# Mikrolysreklamen15.net
KiCad netlist of a schematic drawn in Altium Designer
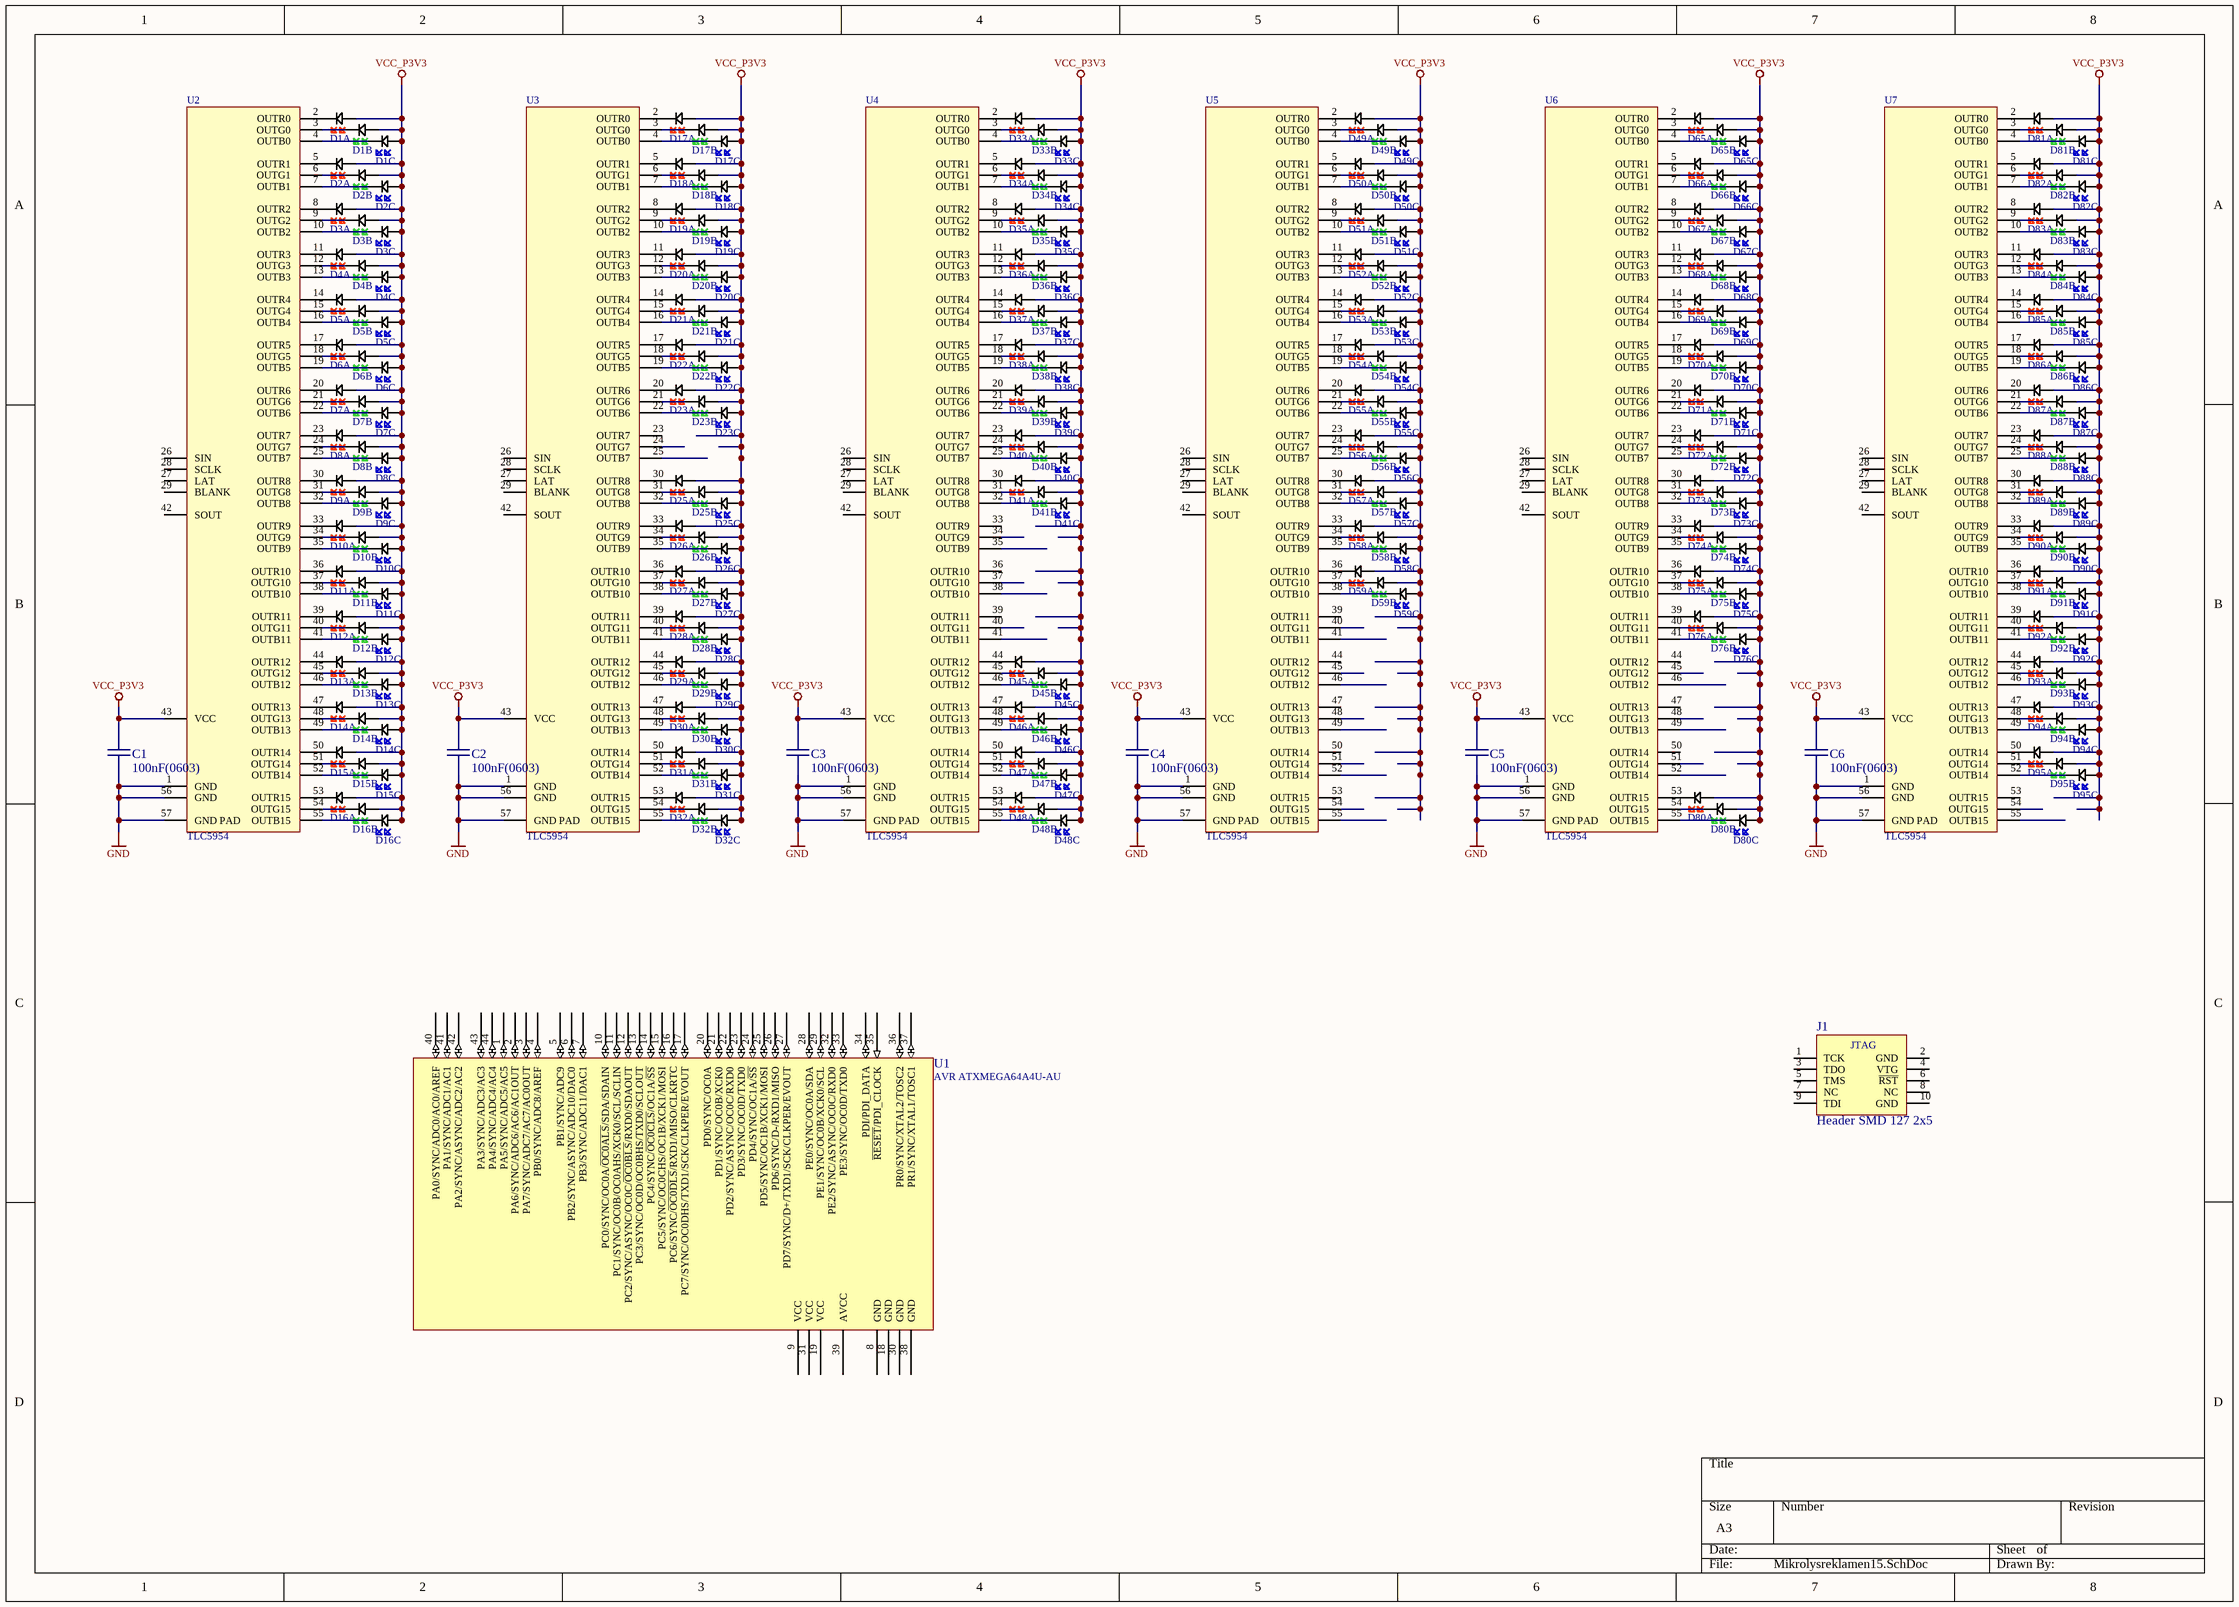
[diagram p0: Mikrolysreklamen15.SchDoc]

(export (version "E")
  (design (tool "Eeschema 10.0.6"))
  (components
    (comp (ref "C1")
      (value "100nF(0603)")
      (footprint "CAPC0603(1608)55_N")
      (description "100nF 0603 5% X7R 50V")
      (libsource (lib "OVLib") (part "CAP"))
    )
    (comp (ref "C2")
      (value "100nF(0603)")
      (footprint "CAPC0603(1608)55_N")
      (description "100nF 0603 5% X7R 50V")
      (libsource (lib "OVLib") (part "CAP"))
    )
    (comp (ref "C3")
      (value "100nF(0603)")
      (footprint "CAPC0603(1608)55_N")
      (description "100nF 0603 5% X7R 50V")
      (libsource (lib "OVLib") (part "CAP"))
    )
    (comp (ref "C4")
      (value "100nF(0603)")
      (footprint "CAPC0603(1608)55_N")
      (description "100nF 0603 5% X7R 50V")
      (libsource (lib "OVLib") (part "CAP"))
    )
    (comp (ref "C5")
      (value "100nF(0603)")
      (footprint "CAPC0603(1608)55_N")
      (description "100nF 0603 5% X7R 50V")
      (libsource (lib "OVLib") (part "CAP"))
    )
    (comp (ref "C6")
      (value "100nF(0603)")
      (footprint "CAPC0603(1608)55_N")
      (description "100nF 0603 5% X7R 50V")
      (libsource (lib "OVLib") (part "CAP"))
    )
    (comp (ref "D1")
      (value "SX-0402-RGB SMD LED")
      (footprint "LED0402SX_N")
      (description "1010 (metric) SMD RGB LED")
      (libsource (lib "OVLib") (part "LED_RGB_CA_CHIP"))
    )
    (comp (ref "D2")
      (value "SX-0402-RGB SMD LED")
      (footprint "LED0402SX_N")
      (description "1010 (metric) SMD RGB LED")
      (libsource (lib "OVLib") (part "LED_RGB_CA_CHIP"))
    )
    (comp (ref "D3")
      (value "SX-0402-RGB SMD LED")
      (footprint "LED0402SX_N")
      (description "1010 (metric) SMD RGB LED")
      (libsource (lib "OVLib") (part "LED_RGB_CA_CHIP"))
    )
    (comp (ref "D4")
      (value "SX-0402-RGB SMD LED")
      (footprint "LED0402SX_N")
      (description "1010 (metric) SMD RGB LED")
      (libsource (lib "OVLib") (part "LED_RGB_CA_CHIP"))
    )
    (comp (ref "D5")
      (value "SX-0402-RGB SMD LED")
      (footprint "LED0402SX_N")
      (description "1010 (metric) SMD RGB LED")
      (libsource (lib "OVLib") (part "LED_RGB_CA_CHIP"))
    )
    (comp (ref "D6")
      (value "SX-0402-RGB SMD LED")
      (footprint "LED0402SX_N")
      (description "1010 (metric) SMD RGB LED")
      (libsource (lib "OVLib") (part "LED_RGB_CA_CHIP"))
    )
    (comp (ref "D7")
      (value "SX-0402-RGB SMD LED")
      (footprint "LED0402SX_N")
      (description "1010 (metric) SMD RGB LED")
      (libsource (lib "OVLib") (part "LED_RGB_CA_CHIP"))
    )
    (comp (ref "D8")
      (value "SX-0402-RGB SMD LED")
      (footprint "LED0402SX_N")
      (description "1010 (metric) SMD RGB LED")
      (libsource (lib "OVLib") (part "LED_RGB_CA_CHIP"))
    )
    (comp (ref "D9")
      (value "SX-0402-RGB SMD LED")
      (footprint "LED0402SX_N")
      (description "1010 (metric) SMD RGB LED")
      (libsource (lib "OVLib") (part "LED_RGB_CA_CHIP"))
    )
    (comp (ref "D10")
      (value "SX-0402-RGB SMD LED")
      (footprint "LED0402SX_N")
      (description "1010 (metric) SMD RGB LED")
      (libsource (lib "OVLib") (part "LED_RGB_CA_CHIP"))
    )
    (comp (ref "D11")
      (value "SX-0402-RGB SMD LED")
      (footprint "LED0402SX_N")
      (description "1010 (metric) SMD RGB LED")
      (libsource (lib "OVLib") (part "LED_RGB_CA_CHIP"))
    )
    (comp (ref "D12")
      (value "SX-0402-RGB SMD LED")
      (footprint "LED0402SX_N")
      (description "1010 (metric) SMD RGB LED")
      (libsource (lib "OVLib") (part "LED_RGB_CA_CHIP"))
    )
    (comp (ref "D13")
      (value "SX-0402-RGB SMD LED")
      (footprint "LED0402SX_N")
      (description "1010 (metric) SMD RGB LED")
      (libsource (lib "OVLib") (part "LED_RGB_CA_CHIP"))
    )
    (comp (ref "D14")
      (value "SX-0402-RGB SMD LED")
      (footprint "LED0402SX_N")
      (description "1010 (metric) SMD RGB LED")
      (libsource (lib "OVLib") (part "LED_RGB_CA_CHIP"))
    )
    (comp (ref "D15")
      (value "SX-0402-RGB SMD LED")
      (footprint "LED0402SX_N")
      (description "1010 (metric) SMD RGB LED")
      (libsource (lib "OVLib") (part "LED_RGB_CA_CHIP"))
    )
    (comp (ref "D16")
      (value "SX-0402-RGB SMD LED")
      (footprint "LED0402SX_N")
      (description "1010 (metric) SMD RGB LED")
      (libsource (lib "OVLib") (part "LED_RGB_CA_CHIP"))
    )
    (comp (ref "D17")
      (value "SX-0402-RGB SMD LED")
      (footprint "LED0402SX_N")
      (description "1010 (metric) SMD RGB LED")
      (libsource (lib "OVLib") (part "LED_RGB_CA_CHIP"))
    )
    (comp (ref "D18")
      (value "SX-0402-RGB SMD LED")
      (footprint "LED0402SX_N")
      (description "1010 (metric) SMD RGB LED")
      (libsource (lib "OVLib") (part "LED_RGB_CA_CHIP"))
    )
    (comp (ref "D19")
      (value "SX-0402-RGB SMD LED")
      (footprint "LED0402SX_N")
      (description "1010 (metric) SMD RGB LED")
      (libsource (lib "OVLib") (part "LED_RGB_CA_CHIP"))
    )
    (comp (ref "D20")
      (value "SX-0402-RGB SMD LED")
      (footprint "LED0402SX_N")
      (description "1010 (metric) SMD RGB LED")
      (libsource (lib "OVLib") (part "LED_RGB_CA_CHIP"))
    )
    (comp (ref "D21")
      (value "SX-0402-RGB SMD LED")
      (footprint "LED0402SX_N")
      (description "1010 (metric) SMD RGB LED")
      (libsource (lib "OVLib") (part "LED_RGB_CA_CHIP"))
    )
    (comp (ref "D22")
      (value "SX-0402-RGB SMD LED")
      (footprint "LED0402SX_N")
      (description "1010 (metric) SMD RGB LED")
      (libsource (lib "OVLib") (part "LED_RGB_CA_CHIP"))
    )
    (comp (ref "D23")
      (value "SX-0402-RGB SMD LED")
      (footprint "LED0402SX_N")
      (description "1010 (metric) SMD RGB LED")
      (libsource (lib "OVLib") (part "LED_RGB_CA_CHIP"))
    )
    (comp (ref "D25")
      (value "SX-0402-RGB SMD LED")
      (footprint "LED0402SX_N")
      (description "1010 (metric) SMD RGB LED")
      (libsource (lib "OVLib") (part "LED_RGB_CA_CHIP"))
    )
    (comp (ref "D26")
      (value "SX-0402-RGB SMD LED")
      (footprint "LED0402SX_N")
      (description "1010 (metric) SMD RGB LED")
      (libsource (lib "OVLib") (part "LED_RGB_CA_CHIP"))
    )
    (comp (ref "D27")
      (value "SX-0402-RGB SMD LED")
      (footprint "LED0402SX_N")
      (description "1010 (metric) SMD RGB LED")
      (libsource (lib "OVLib") (part "LED_RGB_CA_CHIP"))
    )
    (comp (ref "D28")
      (value "SX-0402-RGB SMD LED")
      (footprint "LED0402SX_N")
      (description "1010 (metric) SMD RGB LED")
      (libsource (lib "OVLib") (part "LED_RGB_CA_CHIP"))
    )
    (comp (ref "D29")
      (value "SX-0402-RGB SMD LED")
      (footprint "LED0402SX_N")
      (description "1010 (metric) SMD RGB LED")
      (libsource (lib "OVLib") (part "LED_RGB_CA_CHIP"))
    )
    (comp (ref "D30")
      (value "SX-0402-RGB SMD LED")
      (footprint "LED0402SX_N")
      (description "1010 (metric) SMD RGB LED")
      (libsource (lib "OVLib") (part "LED_RGB_CA_CHIP"))
    )
    (comp (ref "D31")
      (value "SX-0402-RGB SMD LED")
      (footprint "LED0402SX_N")
      (description "1010 (metric) SMD RGB LED")
      (libsource (lib "OVLib") (part "LED_RGB_CA_CHIP"))
    )
    (comp (ref "D32")
      (value "SX-0402-RGB SMD LED")
      (footprint "LED0402SX_N")
      (description "1010 (metric) SMD RGB LED")
      (libsource (lib "OVLib") (part "LED_RGB_CA_CHIP"))
    )
    (comp (ref "D33")
      (value "SX-0402-RGB SMD LED")
      (footprint "LED0402SX_N")
      (description "1010 (metric) SMD RGB LED")
      (libsource (lib "OVLib") (part "LED_RGB_CA_CHIP"))
    )
    (comp (ref "D34")
      (value "SX-0402-RGB SMD LED")
      (footprint "LED0402SX_N")
      (description "1010 (metric) SMD RGB LED")
      (libsource (lib "OVLib") (part "LED_RGB_CA_CHIP"))
    )
    (comp (ref "D35")
      (value "SX-0402-RGB SMD LED")
      (footprint "LED0402SX_N")
      (description "1010 (metric) SMD RGB LED")
      (libsource (lib "OVLib") (part "LED_RGB_CA_CHIP"))
    )
    (comp (ref "D36")
      (value "SX-0402-RGB SMD LED")
      (footprint "LED0402SX_N")
      (description "1010 (metric) SMD RGB LED")
      (libsource (lib "OVLib") (part "LED_RGB_CA_CHIP"))
    )
    (comp (ref "D37")
      (value "SX-0402-RGB SMD LED")
      (footprint "LED0402SX_N")
      (description "1010 (metric) SMD RGB LED")
      (libsource (lib "OVLib") (part "LED_RGB_CA_CHIP"))
    )
    (comp (ref "D38")
      (value "SX-0402-RGB SMD LED")
      (footprint "LED0402SX_N")
      (description "1010 (metric) SMD RGB LED")
      (libsource (lib "OVLib") (part "LED_RGB_CA_CHIP"))
    )
    (comp (ref "D39")
      (value "SX-0402-RGB SMD LED")
      (footprint "LED0402SX_N")
      (description "1010 (metric) SMD RGB LED")
      (libsource (lib "OVLib") (part "LED_RGB_CA_CHIP"))
    )
    (comp (ref "D40")
      (value "SX-0402-RGB SMD LED")
      (footprint "LED0402SX_N")
      (description "1010 (metric) SMD RGB LED")
      (libsource (lib "OVLib") (part "LED_RGB_CA_CHIP"))
    )
    (comp (ref "D41")
      (value "SX-0402-RGB SMD LED")
      (footprint "LED0402SX_N")
      (description "1010 (metric) SMD RGB LED")
      (libsource (lib "OVLib") (part "LED_RGB_CA_CHIP"))
    )
    (comp (ref "D45")
      (value "SX-0402-RGB SMD LED")
      (footprint "LED0402SX_N")
      (description "1010 (metric) SMD RGB LED")
      (libsource (lib "OVLib") (part "LED_RGB_CA_CHIP"))
    )
    (comp (ref "D46")
      (value "SX-0402-RGB SMD LED")
      (footprint "LED0402SX_N")
      (description "1010 (metric) SMD RGB LED")
      (libsource (lib "OVLib") (part "LED_RGB_CA_CHIP"))
    )
    (comp (ref "D47")
      (value "SX-0402-RGB SMD LED")
      (footprint "LED0402SX_N")
      (description "1010 (metric) SMD RGB LED")
      (libsource (lib "OVLib") (part "LED_RGB_CA_CHIP"))
    )
    (comp (ref "D48")
      (value "SX-0402-RGB SMD LED")
      (footprint "LED0402SX_N")
      (description "1010 (metric) SMD RGB LED")
      (libsource (lib "OVLib") (part "LED_RGB_CA_CHIP"))
    )
    (comp (ref "D49")
      (value "SX-0402-RGB SMD LED")
      (footprint "LED0402SX_N")
      (description "1010 (metric) SMD RGB LED")
      (libsource (lib "OVLib") (part "LED_RGB_CA_CHIP"))
    )
    (comp (ref "D50")
      (value "SX-0402-RGB SMD LED")
      (footprint "LED0402SX_N")
      (description "1010 (metric) SMD RGB LED")
      (libsource (lib "OVLib") (part "LED_RGB_CA_CHIP"))
    )
    (comp (ref "D51")
      (value "SX-0402-RGB SMD LED")
      (footprint "LED0402SX_N")
      (description "1010 (metric) SMD RGB LED")
      (libsource (lib "OVLib") (part "LED_RGB_CA_CHIP"))
    )
    (comp (ref "D52")
      (value "SX-0402-RGB SMD LED")
      (footprint "LED0402SX_N")
      (description "1010 (metric) SMD RGB LED")
      (libsource (lib "OVLib") (part "LED_RGB_CA_CHIP"))
    )
    (comp (ref "D53")
      (value "SX-0402-RGB SMD LED")
      (footprint "LED0402SX_N")
      (description "1010 (metric) SMD RGB LED")
      (libsource (lib "OVLib") (part "LED_RGB_CA_CHIP"))
    )
    (comp (ref "D54")
      (value "SX-0402-RGB SMD LED")
      (footprint "LED0402SX_N")
      (description "1010 (metric) SMD RGB LED")
      (libsource (lib "OVLib") (part "LED_RGB_CA_CHIP"))
    )
    (comp (ref "D55")
      (value "SX-0402-RGB SMD LED")
      (footprint "LED0402SX_N")
      (description "1010 (metric) SMD RGB LED")
      (libsource (lib "OVLib") (part "LED_RGB_CA_CHIP"))
    )
    (comp (ref "D56")
      (value "SX-0402-RGB SMD LED")
      (footprint "LED0402SX_N")
      (description "1010 (metric) SMD RGB LED")
      (libsource (lib "OVLib") (part "LED_RGB_CA_CHIP"))
    )
    (comp (ref "D57")
      (value "SX-0402-RGB SMD LED")
      (footprint "LED0402SX_N")
      (description "1010 (metric) SMD RGB LED")
      (libsource (lib "OVLib") (part "LED_RGB_CA_CHIP"))
    )
    (comp (ref "D58")
      (value "SX-0402-RGB SMD LED")
      (footprint "LED0402SX_N")
      (description "1010 (metric) SMD RGB LED")
      (libsource (lib "OVLib") (part "LED_RGB_CA_CHIP"))
    )
    (comp (ref "D59")
      (value "SX-0402-RGB SMD LED")
      (footprint "LED0402SX_N")
      (description "1010 (metric) SMD RGB LED")
      (libsource (lib "OVLib") (part "LED_RGB_CA_CHIP"))
    )
    (comp (ref "D65")
      (value "SX-0402-RGB SMD LED")
      (footprint "LED0402SX_N")
      (description "1010 (metric) SMD RGB LED")
      (libsource (lib "OVLib") (part "LED_RGB_CA_CHIP"))
    )
    (comp (ref "D66")
      (value "SX-0402-RGB SMD LED")
      (footprint "LED0402SX_N")
      (description "1010 (metric) SMD RGB LED")
      (libsource (lib "OVLib") (part "LED_RGB_CA_CHIP"))
    )
    (comp (ref "D67")
      (value "SX-0402-RGB SMD LED")
      (footprint "LED0402SX_N")
      (description "1010 (metric) SMD RGB LED")
      (libsource (lib "OVLib") (part "LED_RGB_CA_CHIP"))
    )
    (comp (ref "D68")
      (value "SX-0402-RGB SMD LED")
      (footprint "LED0402SX_N")
      (description "1010 (metric) SMD RGB LED")
      (libsource (lib "OVLib") (part "LED_RGB_CA_CHIP"))
    )
    (comp (ref "D69")
      (value "SX-0402-RGB SMD LED")
      (footprint "LED0402SX_N")
      (description "1010 (metric) SMD RGB LED")
      (libsource (lib "OVLib") (part "LED_RGB_CA_CHIP"))
    )
    (comp (ref "D70")
      (value "SX-0402-RGB SMD LED")
      (footprint "LED0402SX_N")
      (description "1010 (metric) SMD RGB LED")
      (libsource (lib "OVLib") (part "LED_RGB_CA_CHIP"))
    )
    (comp (ref "D71")
      (value "SX-0402-RGB SMD LED")
      (footprint "LED0402SX_N")
      (description "1010 (metric) SMD RGB LED")
      (libsource (lib "OVLib") (part "LED_RGB_CA_CHIP"))
    )
    (comp (ref "D72")
      (value "SX-0402-RGB SMD LED")
      (footprint "LED0402SX_N")
      (description "1010 (metric) SMD RGB LED")
      (libsource (lib "OVLib") (part "LED_RGB_CA_CHIP"))
    )
    (comp (ref "D73")
      (value "SX-0402-RGB SMD LED")
      (footprint "LED0402SX_N")
      (description "1010 (metric) SMD RGB LED")
      (libsource (lib "OVLib") (part "LED_RGB_CA_CHIP"))
    )
    (comp (ref "D74")
      (value "SX-0402-RGB SMD LED")
      (footprint "LED0402SX_N")
      (description "1010 (metric) SMD RGB LED")
      (libsource (lib "OVLib") (part "LED_RGB_CA_CHIP"))
    )
    (comp (ref "D75")
      (value "SX-0402-RGB SMD LED")
      (footprint "LED0402SX_N")
      (description "1010 (metric) SMD RGB LED")
      (libsource (lib "OVLib") (part "LED_RGB_CA_CHIP"))
    )
    (comp (ref "D76")
      (value "SX-0402-RGB SMD LED")
      (footprint "LED0402SX_N")
      (description "1010 (metric) SMD RGB LED")
      (libsource (lib "OVLib") (part "LED_RGB_CA_CHIP"))
    )
    (comp (ref "D80")
      (value "SX-0402-RGB SMD LED")
      (footprint "LED0402SX_N")
      (description "1010 (metric) SMD RGB LED")
      (libsource (lib "OVLib") (part "LED_RGB_CA_CHIP"))
    )
    (comp (ref "D81")
      (value "SX-0402-RGB SMD LED")
      (footprint "LED0402SX_N")
      (description "1010 (metric) SMD RGB LED")
      (libsource (lib "OVLib") (part "LED_RGB_CA_CHIP"))
    )
    (comp (ref "D82")
      (value "SX-0402-RGB SMD LED")
      (footprint "LED0402SX_N")
      (description "1010 (metric) SMD RGB LED")
      (libsource (lib "OVLib") (part "LED_RGB_CA_CHIP"))
    )
    (comp (ref "D83")
      (value "SX-0402-RGB SMD LED")
      (footprint "LED0402SX_N")
      (description "1010 (metric) SMD RGB LED")
      (libsource (lib "OVLib") (part "LED_RGB_CA_CHIP"))
    )
    (comp (ref "D84")
      (value "SX-0402-RGB SMD LED")
      (footprint "LED0402SX_N")
      (description "1010 (metric) SMD RGB LED")
      (libsource (lib "OVLib") (part "LED_RGB_CA_CHIP"))
    )
    (comp (ref "D85")
      (value "SX-0402-RGB SMD LED")
      (footprint "LED0402SX_N")
      (description "1010 (metric) SMD RGB LED")
      (libsource (lib "OVLib") (part "LED_RGB_CA_CHIP"))
    )
    (comp (ref "D86")
      (value "SX-0402-RGB SMD LED")
      (footprint "LED0402SX_N")
      (description "1010 (metric) SMD RGB LED")
      (libsource (lib "OVLib") (part "LED_RGB_CA_CHIP"))
    )
    (comp (ref "D87")
      (value "SX-0402-RGB SMD LED")
      (footprint "LED0402SX_N")
      (description "1010 (metric) SMD RGB LED")
      (libsource (lib "OVLib") (part "LED_RGB_CA_CHIP"))
    )
    (comp (ref "D88")
      (value "SX-0402-RGB SMD LED")
      (footprint "LED0402SX_N")
      (description "1010 (metric) SMD RGB LED")
      (libsource (lib "OVLib") (part "LED_RGB_CA_CHIP"))
    )
    (comp (ref "D89")
      (value "SX-0402-RGB SMD LED")
      (footprint "LED0402SX_N")
      (description "1010 (metric) SMD RGB LED")
      (libsource (lib "OVLib") (part "LED_RGB_CA_CHIP"))
    )
    (comp (ref "D90")
      (value "SX-0402-RGB SMD LED")
      (footprint "LED0402SX_N")
      (description "1010 (metric) SMD RGB LED")
      (libsource (lib "OVLib") (part "LED_RGB_CA_CHIP"))
    )
    (comp (ref "D91")
      (value "SX-0402-RGB SMD LED")
      (footprint "LED0402SX_N")
      (description "1010 (metric) SMD RGB LED")
      (libsource (lib "OVLib") (part "LED_RGB_CA_CHIP"))
    )
    (comp (ref "D92")
      (value "SX-0402-RGB SMD LED")
      (footprint "LED0402SX_N")
      (description "1010 (metric) SMD RGB LED")
      (libsource (lib "OVLib") (part "LED_RGB_CA_CHIP"))
    )
    (comp (ref "D93")
      (value "SX-0402-RGB SMD LED")
      (footprint "LED0402SX_N")
      (description "1010 (metric) SMD RGB LED")
      (libsource (lib "OVLib") (part "LED_RGB_CA_CHIP"))
    )
    (comp (ref "D94")
      (value "SX-0402-RGB SMD LED")
      (footprint "LED0402SX_N")
      (description "1010 (metric) SMD RGB LED")
      (libsource (lib "OVLib") (part "LED_RGB_CA_CHIP"))
    )
    (comp (ref "D95")
      (value "SX-0402-RGB SMD LED")
      (footprint "LED0402SX_N")
      (description "1010 (metric) SMD RGB LED")
      (libsource (lib "OVLib") (part "LED_RGB_CA_CHIP"))
    )
    (comp (ref "J1")
      (value "Header SMD 127 2x5")
      (footprint "SMDHDRV10P127_2X5_615X330X560B")
      (description "1,27mm Pitch SMD Header")
      (libsource (lib "OVLib") (part "AVRJTAG"))
    )
    (comp (ref "U1")
      (value "AVR ATXMEGA64A4U-AU")
      (footprint "TQFP80P1200X1200X120-44N")
      (description "Mikrokontroller")
      (libsource (lib "OVLib") (part "ATXMEGA-A4U"))
    )
    (comp (ref "U2")
      (value "TLC5954")
      (footprint "TQFN05P815X815X10-56_N")
      (description "48ch LED Driver with Global Brightness Control, LED Open/Short Detection and Power-Save Mode")
      (libsource (lib "OVLib") (part "TLC5954"))
    )
    (comp (ref "U3")
      (value "TLC5954")
      (footprint "TQFN05P815X815X10-56_N")
      (description "48ch LED Driver with Global Brightness Control, LED Open/Short Detection and Power-Save Mode")
      (libsource (lib "OVLib") (part "TLC5954"))
    )
    (comp (ref "U4")
      (value "TLC5954")
      (footprint "TQFN05P815X815X10-56_N")
      (description "48ch LED Driver with Global Brightness Control, LED Open/Short Detection and Power-Save Mode")
      (libsource (lib "OVLib") (part "TLC5954"))
    )
    (comp (ref "U5")
      (value "TLC5954")
      (footprint "TQFN05P815X815X10-56_N")
      (description "48ch LED Driver with Global Brightness Control, LED Open/Short Detection and Power-Save Mode")
      (libsource (lib "OVLib") (part "TLC5954"))
    )
    (comp (ref "U6")
      (value "TLC5954")
      (footprint "TQFN05P815X815X10-56_N")
      (description "48ch LED Driver with Global Brightness Control, LED Open/Short Detection and Power-Save Mode")
      (libsource (lib "OVLib") (part "TLC5954"))
    )
    (comp (ref "U7")
      (value "TLC5954")
      (footprint "TQFN05P815X815X10-56_N")
      (description "48ch LED Driver with Global Brightness Control, LED Open/Short Detection and Power-Save Mode")
      (libsource (lib "OVLib") (part "TLC5954"))
    )
  )
  (nets
    (net (code "1") (name "GND") (class "Default")
      (node (ref "C1") (pin "1") (pinfunction "1_1") (pintype "passive"))
      (node (ref "C2") (pin "1") (pinfunction "1_1") (pintype "passive"))
      (node (ref "C3") (pin "1") (pinfunction "1_1") (pintype "passive"))
      (node (ref "C4") (pin "1") (pinfunction "1_1") (pintype "passive"))
      (node (ref "C5") (pin "1") (pinfunction "1_1") (pintype "passive"))
      (node (ref "C6") (pin "1") (pinfunction "1_1") (pintype "passive"))
      (node (ref "U2") (pin "1") (pinfunction "GND_1") (pintype "passive"))
      (node (ref "U2") (pin "56") (pinfunction "GND_56") (pintype "passive"))
      (node (ref "U2") (pin "57") (pinfunction "GND_PAD_57") (pintype "passive"))
      (node (ref "U3") (pin "1") (pinfunction "GND_1") (pintype "passive"))
      (node (ref "U3") (pin "56") (pinfunction "GND_56") (pintype "passive"))
      (node (ref "U3") (pin "57") (pinfunction "GND_PAD_57") (pintype "passive"))
      (node (ref "U4") (pin "1") (pinfunction "GND_1") (pintype "passive"))
      (node (ref "U4") (pin "56") (pinfunction "GND_56") (pintype "passive"))
      (node (ref "U4") (pin "57") (pinfunction "GND_PAD_57") (pintype "passive"))
      (node (ref "U5") (pin "1") (pinfunction "GND_1") (pintype "passive"))
      (node (ref "U5") (pin "56") (pinfunction "GND_56") (pintype "passive"))
      (node (ref "U5") (pin "57") (pinfunction "GND_PAD_57") (pintype "passive"))
      (node (ref "U6") (pin "1") (pinfunction "GND_1") (pintype "passive"))
      (node (ref "U6") (pin "56") (pinfunction "GND_56") (pintype "passive"))
      (node (ref "U6") (pin "57") (pinfunction "GND_PAD_57") (pintype "passive"))
      (node (ref "U7") (pin "1") (pinfunction "GND_1") (pintype "passive"))
      (node (ref "U7") (pin "56") (pinfunction "GND_56") (pintype "passive"))
      (node (ref "U7") (pin "57") (pinfunction "GND_PAD_57") (pintype "passive"))
    )
    (net (code "2") (name "Net-(U2-OUTB0)") (class "Default")
      (node (ref "D1") (pin "4") (pinfunction "4_4") (pintype "passive"))
      (node (ref "U2") (pin "4") (pinfunction "OUTB0_4") (pintype "passive"))
    )
    (net (code "3") (name "Net-(U2-OUTB1)") (class "Default")
      (node (ref "D2") (pin "4") (pinfunction "4_4") (pintype "passive"))
      (node (ref "U2") (pin "7") (pinfunction "OUTB1_7") (pintype "passive"))
    )
    (net (code "4") (name "Net-(U2-OUTB2)") (class "Default")
      (node (ref "D3") (pin "4") (pinfunction "4_4") (pintype "passive"))
      (node (ref "U2") (pin "10") (pinfunction "OUTB2_10") (pintype "passive"))
    )
    (net (code "5") (name "Net-(U2-OUTB3)") (class "Default")
      (node (ref "D4") (pin "4") (pinfunction "4_4") (pintype "passive"))
      (node (ref "U2") (pin "13") (pinfunction "OUTB3_13") (pintype "passive"))
    )
    (net (code "6") (name "Net-(U2-OUTB4)") (class "Default")
      (node (ref "D5") (pin "4") (pinfunction "4_4") (pintype "passive"))
      (node (ref "U2") (pin "16") (pinfunction "OUTB4_16") (pintype "passive"))
    )
    (net (code "7") (name "Net-(U2-OUTB5)") (class "Default")
      (node (ref "D6") (pin "4") (pinfunction "4_4") (pintype "passive"))
      (node (ref "U2") (pin "19") (pinfunction "OUTB5_19") (pintype "passive"))
    )
    (net (code "8") (name "Net-(U2-OUTB6)") (class "Default")
      (node (ref "D7") (pin "4") (pinfunction "4_4") (pintype "passive"))
      (node (ref "U2") (pin "22") (pinfunction "OUTB6_22") (pintype "passive"))
    )
    (net (code "9") (name "Net-(U2-OUTB7)") (class "Default")
      (node (ref "D8") (pin "4") (pinfunction "4_4") (pintype "passive"))
      (node (ref "U2") (pin "25") (pinfunction "OUTB7_25") (pintype "passive"))
    )
    (net (code "10") (name "Net-(U2-OUTB8)") (class "Default")
      (node (ref "D9") (pin "4") (pinfunction "4_4") (pintype "passive"))
      (node (ref "U2") (pin "32") (pinfunction "OUTB8_32") (pintype "passive"))
    )
    (net (code "11") (name "Net-(U2-OUTB9)") (class "Default")
      (node (ref "D10") (pin "4") (pinfunction "4_4") (pintype "passive"))
      (node (ref "U2") (pin "35") (pinfunction "OUTB9_35") (pintype "passive"))
    )
    (net (code "12") (name "Net-(U2-OUTB10)") (class "Default")
      (node (ref "D11") (pin "4") (pinfunction "4_4") (pintype "passive"))
      (node (ref "U2") (pin "38") (pinfunction "OUTB10_38") (pintype "passive"))
    )
    (net (code "13") (name "Net-(U2-OUTB11)") (class "Default")
      (node (ref "D12") (pin "4") (pinfunction "4_4") (pintype "passive"))
      (node (ref "U2") (pin "41") (pinfunction "OUTB11_41") (pintype "passive"))
    )
    (net (code "14") (name "Net-(U2-OUTB12)") (class "Default")
      (node (ref "D13") (pin "4") (pinfunction "4_4") (pintype "passive"))
      (node (ref "U2") (pin "46") (pinfunction "OUTB12_46") (pintype "passive"))
    )
    (net (code "15") (name "Net-(U2-OUTB13)") (class "Default")
      (node (ref "D14") (pin "4") (pinfunction "4_4") (pintype "passive"))
      (node (ref "U2") (pin "49") (pinfunction "OUTB13_49") (pintype "passive"))
    )
    (net (code "16") (name "Net-(U2-OUTB14)") (class "Default")
      (node (ref "D15") (pin "4") (pinfunction "4_4") (pintype "passive"))
      (node (ref "U2") (pin "52") (pinfunction "OUTB14_52") (pintype "passive"))
    )
    (net (code "17") (name "Net-(U2-OUTB15)") (class "Default")
      (node (ref "D16") (pin "4") (pinfunction "4_4") (pintype "passive"))
      (node (ref "U2") (pin "55") (pinfunction "OUTB15_55") (pintype "passive"))
    )
    (net (code "18") (name "Net-(U2-OUTG0)") (class "Default")
      (node (ref "D1") (pin "3") (pinfunction "3_3") (pintype "passive"))
      (node (ref "U2") (pin "3") (pinfunction "OUTG0_3") (pintype "passive"))
    )
    (net (code "19") (name "Net-(U2-OUTG1)") (class "Default")
      (node (ref "D2") (pin "3") (pinfunction "3_3") (pintype "passive"))
      (node (ref "U2") (pin "6") (pinfunction "OUTG1_6") (pintype "passive"))
    )
    (net (code "20") (name "Net-(U2-OUTG2)") (class "Default")
      (node (ref "D3") (pin "3") (pinfunction "3_3") (pintype "passive"))
      (node (ref "U2") (pin "9") (pinfunction "OUTG2_9") (pintype "passive"))
    )
    (net (code "21") (name "Net-(U2-OUTG3)") (class "Default")
      (node (ref "D4") (pin "3") (pinfunction "3_3") (pintype "passive"))
      (node (ref "U2") (pin "12") (pinfunction "OUTG3_12") (pintype "passive"))
    )
    (net (code "22") (name "Net-(U2-OUTG4)") (class "Default")
      (node (ref "D5") (pin "3") (pinfunction "3_3") (pintype "passive"))
      (node (ref "U2") (pin "15") (pinfunction "OUTG4_15") (pintype "passive"))
    )
    (net (code "23") (name "Net-(U2-OUTG5)") (class "Default")
      (node (ref "D6") (pin "3") (pinfunction "3_3") (pintype "passive"))
      (node (ref "U2") (pin "18") (pinfunction "OUTG5_18") (pintype "passive"))
    )
    (net (code "24") (name "Net-(U2-OUTG6)") (class "Default")
      (node (ref "D7") (pin "3") (pinfunction "3_3") (pintype "passive"))
      (node (ref "U2") (pin "21") (pinfunction "OUTG6_21") (pintype "passive"))
    )
    (net (code "25") (name "Net-(U2-OUTG7)") (class "Default")
      (node (ref "D8") (pin "3") (pinfunction "3_3") (pintype "passive"))
      (node (ref "U2") (pin "24") (pinfunction "OUTG7_24") (pintype "passive"))
    )
    (net (code "26") (name "Net-(U2-OUTG8)") (class "Default")
      (node (ref "D9") (pin "3") (pinfunction "3_3") (pintype "passive"))
      (node (ref "U2") (pin "31") (pinfunction "OUTG8_31") (pintype "passive"))
    )
    (net (code "27") (name "Net-(U2-OUTG9)") (class "Default")
      (node (ref "D10") (pin "3") (pinfunction "3_3") (pintype "passive"))
      (node (ref "U2") (pin "34") (pinfunction "OUTG9_34") (pintype "passive"))
    )
    (net (code "28") (name "Net-(U2-OUTG10)") (class "Default")
      (node (ref "D11") (pin "3") (pinfunction "3_3") (pintype "passive"))
      (node (ref "U2") (pin "37") (pinfunction "OUTG10_37") (pintype "passive"))
    )
    (net (code "29") (name "Net-(U2-OUTG11)") (class "Default")
      (node (ref "D12") (pin "3") (pinfunction "3_3") (pintype "passive"))
      (node (ref "U2") (pin "40") (pinfunction "OUTG11_40") (pintype "passive"))
    )
    (net (code "30") (name "Net-(U2-OUTG12)") (class "Default")
      (node (ref "D13") (pin "3") (pinfunction "3_3") (pintype "passive"))
      (node (ref "U2") (pin "45") (pinfunction "OUTG12_45") (pintype "passive"))
    )
    (net (code "31") (name "Net-(U2-OUTG13)") (class "Default")
      (node (ref "D14") (pin "3") (pinfunction "3_3") (pintype "passive"))
      (node (ref "U2") (pin "48") (pinfunction "OUTG13_48") (pintype "passive"))
    )
    (net (code "32") (name "Net-(U2-OUTG14)") (class "Default")
      (node (ref "D15") (pin "3") (pinfunction "3_3") (pintype "passive"))
      (node (ref "U2") (pin "51") (pinfunction "OUTG14_51") (pintype "passive"))
    )
    (net (code "33") (name "Net-(U2-OUTG15)") (class "Default")
      (node (ref "D16") (pin "3") (pinfunction "3_3") (pintype "passive"))
      (node (ref "U2") (pin "54") (pinfunction "OUTG15_54") (pintype "passive"))
    )
    (net (code "34") (name "Net-(U2-OUTR0)") (class "Default")
      (node (ref "D1") (pin "2") (pinfunction "2_2") (pintype "passive"))
      (node (ref "U2") (pin "2") (pinfunction "OUTR0_2") (pintype "passive"))
    )
    (net (code "35") (name "Net-(U2-OUTR1)") (class "Default")
      (node (ref "D2") (pin "2") (pinfunction "2_2") (pintype "passive"))
      (node (ref "U2") (pin "5") (pinfunction "OUTR1_5") (pintype "passive"))
    )
    (net (code "36") (name "Net-(U2-OUTR2)") (class "Default")
      (node (ref "D3") (pin "2") (pinfunction "2_2") (pintype "passive"))
      (node (ref "U2") (pin "8") (pinfunction "OUTR2_8") (pintype "passive"))
    )
    (net (code "37") (name "Net-(U2-OUTR3)") (class "Default")
      (node (ref "D4") (pin "2") (pinfunction "2_2") (pintype "passive"))
      (node (ref "U2") (pin "11") (pinfunction "OUTR3_11") (pintype "passive"))
    )
    (net (code "38") (name "Net-(U2-OUTR4)") (class "Default")
      (node (ref "D5") (pin "2") (pinfunction "2_2") (pintype "passive"))
      (node (ref "U2") (pin "14") (pinfunction "OUTR4_14") (pintype "passive"))
    )
    (net (code "39") (name "Net-(U2-OUTR5)") (class "Default")
      (node (ref "D6") (pin "2") (pinfunction "2_2") (pintype "passive"))
      (node (ref "U2") (pin "17") (pinfunction "OUTR5_17") (pintype "passive"))
    )
    (net (code "40") (name "Net-(U2-OUTR6)") (class "Default")
      (node (ref "D7") (pin "2") (pinfunction "2_2") (pintype "passive"))
      (node (ref "U2") (pin "20") (pinfunction "OUTR6_20") (pintype "passive"))
    )
    (net (code "41") (name "Net-(U2-OUTR7)") (class "Default")
      (node (ref "D8") (pin "2") (pinfunction "2_2") (pintype "passive"))
      (node (ref "U2") (pin "23") (pinfunction "OUTR7_23") (pintype "passive"))
    )
    (net (code "42") (name "Net-(U2-OUTR8)") (class "Default")
      (node (ref "D9") (pin "2") (pinfunction "2_2") (pintype "passive"))
      (node (ref "U2") (pin "30") (pinfunction "OUTR8_30") (pintype "passive"))
    )
    (net (code "43") (name "Net-(U2-OUTR9)") (class "Default")
      (node (ref "D10") (pin "2") (pinfunction "2_2") (pintype "passive"))
      (node (ref "U2") (pin "33") (pinfunction "OUTR9_33") (pintype "passive"))
    )
    (net (code "44") (name "Net-(U2-OUTR10)") (class "Default")
      (node (ref "D11") (pin "2") (pinfunction "2_2") (pintype "passive"))
      (node (ref "U2") (pin "36") (pinfunction "OUTR10_36") (pintype "passive"))
    )
    (net (code "45") (name "Net-(U2-OUTR11)") (class "Default")
      (node (ref "D12") (pin "2") (pinfunction "2_2") (pintype "passive"))
      (node (ref "U2") (pin "39") (pinfunction "OUTR11_39") (pintype "passive"))
    )
    (net (code "46") (name "Net-(U2-OUTR12)") (class "Default")
      (node (ref "D13") (pin "2") (pinfunction "2_2") (pintype "passive"))
      (node (ref "U2") (pin "44") (pinfunction "OUTR12_44") (pintype "passive"))
    )
    (net (code "47") (name "Net-(U2-OUTR13)") (class "Default")
      (node (ref "D14") (pin "2") (pinfunction "2_2") (pintype "passive"))
      (node (ref "U2") (pin "47") (pinfunction "OUTR13_47") (pintype "passive"))
    )
    (net (code "48") (name "Net-(U2-OUTR14)") (class "Default")
      (node (ref "D15") (pin "2") (pinfunction "2_2") (pintype "passive"))
      (node (ref "U2") (pin "50") (pinfunction "OUTR14_50") (pintype "passive"))
    )
    (net (code "49") (name "Net-(U2-OUTR15)") (class "Default")
      (node (ref "D16") (pin "2") (pinfunction "2_2") (pintype "passive"))
      (node (ref "U2") (pin "53") (pinfunction "OUTR15_53") (pintype "passive"))
    )
    (net (code "50") (name "Net-(U3-OUTB0)") (class "Default")
      (node (ref "D17") (pin "4") (pinfunction "4_4") (pintype "passive"))
      (node (ref "U3") (pin "4") (pinfunction "OUTB0_4") (pintype "passive"))
    )
    (net (code "51") (name "Net-(U3-OUTB1)") (class "Default")
      (node (ref "D18") (pin "4") (pinfunction "4_4") (pintype "passive"))
      (node (ref "U3") (pin "7") (pinfunction "OUTB1_7") (pintype "passive"))
    )
    (net (code "52") (name "Net-(U3-OUTB2)") (class "Default")
      (node (ref "D19") (pin "4") (pinfunction "4_4") (pintype "passive"))
      (node (ref "U3") (pin "10") (pinfunction "OUTB2_10") (pintype "passive"))
    )
    (net (code "53") (name "Net-(U3-OUTB3)") (class "Default")
      (node (ref "D20") (pin "4") (pinfunction "4_4") (pintype "passive"))
      (node (ref "U3") (pin "13") (pinfunction "OUTB3_13") (pintype "passive"))
    )
    (net (code "54") (name "Net-(U3-OUTB4)") (class "Default")
      (node (ref "D21") (pin "4") (pinfunction "4_4") (pintype "passive"))
      (node (ref "U3") (pin "16") (pinfunction "OUTB4_16") (pintype "passive"))
    )
    (net (code "55") (name "Net-(U3-OUTB5)") (class "Default")
      (node (ref "D22") (pin "4") (pinfunction "4_4") (pintype "passive"))
      (node (ref "U3") (pin "19") (pinfunction "OUTB5_19") (pintype "passive"))
    )
    (net (code "56") (name "Net-(U3-OUTB6)") (class "Default")
      (node (ref "D23") (pin "4") (pinfunction "4_4") (pintype "passive"))
      (node (ref "U3") (pin "22") (pinfunction "OUTB6_22") (pintype "passive"))
    )
    (net (code "57") (name "Net-(U3-OUTB8)") (class "Default")
      (node (ref "D25") (pin "4") (pinfunction "4_4") (pintype "passive"))
      (node (ref "U3") (pin "32") (pinfunction "OUTB8_32") (pintype "passive"))
    )
    (net (code "58") (name "Net-(U3-OUTB9)") (class "Default")
      (node (ref "D26") (pin "4") (pinfunction "4_4") (pintype "passive"))
      (node (ref "U3") (pin "35") (pinfunction "OUTB9_35") (pintype "passive"))
    )
    (net (code "59") (name "Net-(U3-OUTB10)") (class "Default")
      (node (ref "D27") (pin "4") (pinfunction "4_4") (pintype "passive"))
      (node (ref "U3") (pin "38") (pinfunction "OUTB10_38") (pintype "passive"))
    )
    (net (code "60") (name "Net-(U3-OUTB11)") (class "Default")
      (node (ref "D28") (pin "4") (pinfunction "4_4") (pintype "passive"))
      (node (ref "U3") (pin "41") (pinfunction "OUTB11_41") (pintype "passive"))
    )
    (net (code "61") (name "Net-(U3-OUTB12)") (class "Default")
      (node (ref "D29") (pin "4") (pinfunction "4_4") (pintype "passive"))
      (node (ref "U3") (pin "46") (pinfunction "OUTB12_46") (pintype "passive"))
    )
    (net (code "62") (name "Net-(U3-OUTB13)") (class "Default")
      (node (ref "D30") (pin "4") (pinfunction "4_4") (pintype "passive"))
      (node (ref "U3") (pin "49") (pinfunction "OUTB13_49") (pintype "passive"))
    )
    (net (code "63") (name "Net-(U3-OUTB14)") (class "Default")
      (node (ref "D31") (pin "4") (pinfunction "4_4") (pintype "passive"))
      (node (ref "U3") (pin "52") (pinfunction "OUTB14_52") (pintype "passive"))
    )
    (net (code "64") (name "Net-(U3-OUTB15)") (class "Default")
      (node (ref "D32") (pin "4") (pinfunction "4_4") (pintype "passive"))
      (node (ref "U3") (pin "55") (pinfunction "OUTB15_55") (pintype "passive"))
    )
    (net (code "65") (name "Net-(U3-OUTG0)") (class "Default")
      (node (ref "D17") (pin "3") (pinfunction "3_3") (pintype "passive"))
      (node (ref "U3") (pin "3") (pinfunction "OUTG0_3") (pintype "passive"))
    )
    (net (code "66") (name "Net-(U3-OUTG1)") (class "Default")
      (node (ref "D18") (pin "3") (pinfunction "3_3") (pintype "passive"))
      (node (ref "U3") (pin "6") (pinfunction "OUTG1_6") (pintype "passive"))
    )
    (net (code "67") (name "Net-(U3-OUTG2)") (class "Default")
      (node (ref "D19") (pin "3") (pinfunction "3_3") (pintype "passive"))
      (node (ref "U3") (pin "9") (pinfunction "OUTG2_9") (pintype "passive"))
    )
    (net (code "68") (name "Net-(U3-OUTG3)") (class "Default")
      (node (ref "D20") (pin "3") (pinfunction "3_3") (pintype "passive"))
      (node (ref "U3") (pin "12") (pinfunction "OUTG3_12") (pintype "passive"))
    )
    (net (code "69") (name "Net-(U3-OUTG4)") (class "Default")
      (node (ref "D21") (pin "3") (pinfunction "3_3") (pintype "passive"))
      (node (ref "U3") (pin "15") (pinfunction "OUTG4_15") (pintype "passive"))
    )
    (net (code "70") (name "Net-(U3-OUTG5)") (class "Default")
      (node (ref "D22") (pin "3") (pinfunction "3_3") (pintype "passive"))
      (node (ref "U3") (pin "18") (pinfunction "OUTG5_18") (pintype "passive"))
    )
    (net (code "71") (name "Net-(U3-OUTG6)") (class "Default")
      (node (ref "D23") (pin "3") (pinfunction "3_3") (pintype "passive"))
      (node (ref "U3") (pin "21") (pinfunction "OUTG6_21") (pintype "passive"))
    )
    (net (code "72") (name "Net-(U3-OUTG8)") (class "Default")
      (node (ref "D25") (pin "3") (pinfunction "3_3") (pintype "passive"))
      (node (ref "U3") (pin "31") (pinfunction "OUTG8_31") (pintype "passive"))
    )
    (net (code "73") (name "Net-(U3-OUTG9)") (class "Default")
      (node (ref "D26") (pin "3") (pinfunction "3_3") (pintype "passive"))
      (node (ref "U3") (pin "34") (pinfunction "OUTG9_34") (pintype "passive"))
    )
    (net (code "74") (name "Net-(U3-OUTG10)") (class "Default")
      (node (ref "D27") (pin "3") (pinfunction "3_3") (pintype "passive"))
      (node (ref "U3") (pin "37") (pinfunction "OUTG10_37") (pintype "passive"))
    )
    (net (code "75") (name "Net-(U3-OUTG11)") (class "Default")
      (node (ref "D28") (pin "3") (pinfunction "3_3") (pintype "passive"))
      (node (ref "U3") (pin "40") (pinfunction "OUTG11_40") (pintype "passive"))
    )
    (net (code "76") (name "Net-(U3-OUTG12)") (class "Default")
      (node (ref "D29") (pin "3") (pinfunction "3_3") (pintype "passive"))
      (node (ref "U3") (pin "45") (pinfunction "OUTG12_45") (pintype "passive"))
    )
    (net (code "77") (name "Net-(U3-OUTG13)") (class "Default")
      (node (ref "D30") (pin "3") (pinfunction "3_3") (pintype "passive"))
      (node (ref "U3") (pin "48") (pinfunction "OUTG13_48") (pintype "passive"))
    )
    (net (code "78") (name "Net-(U3-OUTG14)") (class "Default")
      (node (ref "D31") (pin "3") (pinfunction "3_3") (pintype "passive"))
      (node (ref "U3") (pin "51") (pinfunction "OUTG14_51") (pintype "passive"))
    )
    (net (code "79") (name "Net-(U3-OUTG15)") (class "Default")
      (node (ref "D32") (pin "3") (pinfunction "3_3") (pintype "passive"))
      (node (ref "U3") (pin "54") (pinfunction "OUTG15_54") (pintype "passive"))
    )
    (net (code "80") (name "Net-(U3-OUTR0)") (class "Default")
      (node (ref "D17") (pin "2") (pinfunction "2_2") (pintype "passive"))
      (node (ref "U3") (pin "2") (pinfunction "OUTR0_2") (pintype "passive"))
    )
    (net (code "81") (name "Net-(U3-OUTR1)") (class "Default")
      (node (ref "D18") (pin "2") (pinfunction "2_2") (pintype "passive"))
      (node (ref "U3") (pin "5") (pinfunction "OUTR1_5") (pintype "passive"))
    )
    (net (code "82") (name "Net-(U3-OUTR2)") (class "Default")
      (node (ref "D19") (pin "2") (pinfunction "2_2") (pintype "passive"))
      (node (ref "U3") (pin "8") (pinfunction "OUTR2_8") (pintype "passive"))
    )
    (net (code "83") (name "Net-(U3-OUTR3)") (class "Default")
      (node (ref "D20") (pin "2") (pinfunction "2_2") (pintype "passive"))
      (node (ref "U3") (pin "11") (pinfunction "OUTR3_11") (pintype "passive"))
    )
    (net (code "84") (name "Net-(U3-OUTR4)") (class "Default")
      (node (ref "D21") (pin "2") (pinfunction "2_2") (pintype "passive"))
      (node (ref "U3") (pin "14") (pinfunction "OUTR4_14") (pintype "passive"))
    )
    (net (code "85") (name "Net-(U3-OUTR5)") (class "Default")
      (node (ref "D22") (pin "2") (pinfunction "2_2") (pintype "passive"))
      (node (ref "U3") (pin "17") (pinfunction "OUTR5_17") (pintype "passive"))
    )
    (net (code "86") (name "Net-(U3-OUTR6)") (class "Default")
      (node (ref "D23") (pin "2") (pinfunction "2_2") (pintype "passive"))
      (node (ref "U3") (pin "20") (pinfunction "OUTR6_20") (pintype "passive"))
    )
    (net (code "87") (name "Net-(U3-OUTR8)") (class "Default")
      (node (ref "D25") (pin "2") (pinfunction "2_2") (pintype "passive"))
      (node (ref "U3") (pin "30") (pinfunction "OUTR8_30") (pintype "passive"))
    )
    (net (code "88") (name "Net-(U3-OUTR9)") (class "Default")
      (node (ref "D26") (pin "2") (pinfunction "2_2") (pintype "passive"))
      (node (ref "U3") (pin "33") (pinfunction "OUTR9_33") (pintype "passive"))
    )
    (net (code "89") (name "Net-(U3-OUTR10)") (class "Default")
      (node (ref "D27") (pin "2") (pinfunction "2_2") (pintype "passive"))
      (node (ref "U3") (pin "36") (pinfunction "OUTR10_36") (pintype "passive"))
    )
    (net (code "90") (name "Net-(U3-OUTR11)") (class "Default")
      (node (ref "D28") (pin "2") (pinfunction "2_2") (pintype "passive"))
      (node (ref "U3") (pin "39") (pinfunction "OUTR11_39") (pintype "passive"))
    )
    (net (code "91") (name "Net-(U3-OUTR12)") (class "Default")
      (node (ref "D29") (pin "2") (pinfunction "2_2") (pintype "passive"))
      (node (ref "U3") (pin "44") (pinfunction "OUTR12_44") (pintype "passive"))
    )
    (net (code "92") (name "Net-(U3-OUTR13)") (class "Default")
      (node (ref "D30") (pin "2") (pinfunction "2_2") (pintype "passive"))
      (node (ref "U3") (pin "47") (pinfunction "OUTR13_47") (pintype "passive"))
    )
    (net (code "93") (name "Net-(U3-OUTR14)") (class "Default")
      (node (ref "D31") (pin "2") (pinfunction "2_2") (pintype "passive"))
      (node (ref "U3") (pin "50") (pinfunction "OUTR14_50") (pintype "passive"))
    )
    (net (code "94") (name "Net-(U3-OUTR15)") (class "Default")
      (node (ref "D32") (pin "2") (pinfunction "2_2") (pintype "passive"))
      (node (ref "U3") (pin "53") (pinfunction "OUTR15_53") (pintype "passive"))
    )
    (net (code "95") (name "Net-(U4-OUTB0)") (class "Default")
      (node (ref "D33") (pin "4") (pinfunction "4_4") (pintype "passive"))
      (node (ref "U4") (pin "4") (pinfunction "OUTB0_4") (pintype "passive"))
    )
    (net (code "96") (name "Net-(U4-OUTB1)") (class "Default")
      (node (ref "D34") (pin "4") (pinfunction "4_4") (pintype "passive"))
      (node (ref "U4") (pin "7") (pinfunction "OUTB1_7") (pintype "passive"))
    )
    (net (code "97") (name "Net-(U4-OUTB2)") (class "Default")
      (node (ref "D35") (pin "4") (pinfunction "4_4") (pintype "passive"))
      (node (ref "U4") (pin "10") (pinfunction "OUTB2_10") (pintype "passive"))
    )
    (net (code "98") (name "Net-(U4-OUTB3)") (class "Default")
      (node (ref "D36") (pin "4") (pinfunction "4_4") (pintype "passive"))
      (node (ref "U4") (pin "13") (pinfunction "OUTB3_13") (pintype "passive"))
    )
    (net (code "99") (name "Net-(U4-OUTB4)") (class "Default")
      (node (ref "D37") (pin "4") (pinfunction "4_4") (pintype "passive"))
      (node (ref "U4") (pin "16") (pinfunction "OUTB4_16") (pintype "passive"))
    )
    (net (code "100") (name "Net-(U4-OUTB5)") (class "Default")
      (node (ref "D38") (pin "4") (pinfunction "4_4") (pintype "passive"))
      (node (ref "U4") (pin "19") (pinfunction "OUTB5_19") (pintype "passive"))
    )
    (net (code "101") (name "Net-(U4-OUTB6)") (class "Default")
      (node (ref "D39") (pin "4") (pinfunction "4_4") (pintype "passive"))
      (node (ref "U4") (pin "22") (pinfunction "OUTB6_22") (pintype "passive"))
    )
    (net (code "102") (name "Net-(U4-OUTB7)") (class "Default")
      (node (ref "D40") (pin "4") (pinfunction "4_4") (pintype "passive"))
      (node (ref "U4") (pin "25") (pinfunction "OUTB7_25") (pintype "passive"))
    )
    (net (code "103") (name "Net-(U4-OUTB8)") (class "Default")
      (node (ref "D41") (pin "4") (pinfunction "4_4") (pintype "passive"))
      (node (ref "U4") (pin "32") (pinfunction "OUTB8_32") (pintype "passive"))
    )
    (net (code "104") (name "Net-(U4-OUTB12)") (class "Default")
      (node (ref "D45") (pin "4") (pinfunction "4_4") (pintype "passive"))
      (node (ref "U4") (pin "46") (pinfunction "OUTB12_46") (pintype "passive"))
    )
    (net (code "105") (name "Net-(U4-OUTB13)") (class "Default")
      (node (ref "D46") (pin "4") (pinfunction "4_4") (pintype "passive"))
      (node (ref "U4") (pin "49") (pinfunction "OUTB13_49") (pintype "passive"))
    )
    (net (code "106") (name "Net-(U4-OUTB14)") (class "Default")
      (node (ref "D47") (pin "4") (pinfunction "4_4") (pintype "passive"))
      (node (ref "U4") (pin "52") (pinfunction "OUTB14_52") (pintype "passive"))
    )
    (net (code "107") (name "Net-(U4-OUTB15)") (class "Default")
      (node (ref "D48") (pin "4") (pinfunction "4_4") (pintype "passive"))
      (node (ref "U4") (pin "55") (pinfunction "OUTB15_55") (pintype "passive"))
    )
    (net (code "108") (name "Net-(U4-OUTG0)") (class "Default")
      (node (ref "D33") (pin "3") (pinfunction "3_3") (pintype "passive"))
      (node (ref "U4") (pin "3") (pinfunction "OUTG0_3") (pintype "passive"))
    )
    (net (code "109") (name "Net-(U4-OUTG1)") (class "Default")
      (node (ref "D34") (pin "3") (pinfunction "3_3") (pintype "passive"))
      (node (ref "U4") (pin "6") (pinfunction "OUTG1_6") (pintype "passive"))
    )
    (net (code "110") (name "Net-(U4-OUTG2)") (class "Default")
      (node (ref "D35") (pin "3") (pinfunction "3_3") (pintype "passive"))
      (node (ref "U4") (pin "9") (pinfunction "OUTG2_9") (pintype "passive"))
    )
    (net (code "111") (name "Net-(U4-OUTG3)") (class "Default")
      (node (ref "D36") (pin "3") (pinfunction "3_3") (pintype "passive"))
      (node (ref "U4") (pin "12") (pinfunction "OUTG3_12") (pintype "passive"))
    )
    (net (code "112") (name "Net-(U4-OUTG4)") (class "Default")
      (node (ref "D37") (pin "3") (pinfunction "3_3") (pintype "passive"))
      (node (ref "U4") (pin "15") (pinfunction "OUTG4_15") (pintype "passive"))
    )
    (net (code "113") (name "Net-(U4-OUTG5)") (class "Default")
      (node (ref "D38") (pin "3") (pinfunction "3_3") (pintype "passive"))
      (node (ref "U4") (pin "18") (pinfunction "OUTG5_18") (pintype "passive"))
    )
    (net (code "114") (name "Net-(U4-OUTG6)") (class "Default")
      (node (ref "D39") (pin "3") (pinfunction "3_3") (pintype "passive"))
      (node (ref "U4") (pin "21") (pinfunction "OUTG6_21") (pintype "passive"))
    )
    (net (code "115") (name "Net-(U4-OUTG7)") (class "Default")
      (node (ref "D40") (pin "3") (pinfunction "3_3") (pintype "passive"))
      (node (ref "U4") (pin "24") (pinfunction "OUTG7_24") (pintype "passive"))
    )
    (net (code "116") (name "Net-(U4-OUTG8)") (class "Default")
      (node (ref "D41") (pin "3") (pinfunction "3_3") (pintype "passive"))
      (node (ref "U4") (pin "31") (pinfunction "OUTG8_31") (pintype "passive"))
    )
    (net (code "117") (name "Net-(U4-OUTG12)") (class "Default")
      (node (ref "D45") (pin "3") (pinfunction "3_3") (pintype "passive"))
      (node (ref "U4") (pin "45") (pinfunction "OUTG12_45") (pintype "passive"))
    )
    (net (code "118") (name "Net-(U4-OUTG13)") (class "Default")
      (node (ref "D46") (pin "3") (pinfunction "3_3") (pintype "passive"))
      (node (ref "U4") (pin "48") (pinfunction "OUTG13_48") (pintype "passive"))
    )
    (net (code "119") (name "Net-(U4-OUTG14)") (class "Default")
      (node (ref "D47") (pin "3") (pinfunction "3_3") (pintype "passive"))
      (node (ref "U4") (pin "51") (pinfunction "OUTG14_51") (pintype "passive"))
    )
    (net (code "120") (name "Net-(U4-OUTG15)") (class "Default")
      (node (ref "D48") (pin "3") (pinfunction "3_3") (pintype "passive"))
      (node (ref "U4") (pin "54") (pinfunction "OUTG15_54") (pintype "passive"))
    )
    (net (code "121") (name "Net-(U4-OUTR0)") (class "Default")
      (node (ref "D33") (pin "2") (pinfunction "2_2") (pintype "passive"))
      (node (ref "U4") (pin "2") (pinfunction "OUTR0_2") (pintype "passive"))
    )
    (net (code "122") (name "Net-(U4-OUTR1)") (class "Default")
      (node (ref "D34") (pin "2") (pinfunction "2_2") (pintype "passive"))
      (node (ref "U4") (pin "5") (pinfunction "OUTR1_5") (pintype "passive"))
    )
    (net (code "123") (name "Net-(U4-OUTR2)") (class "Default")
      (node (ref "D35") (pin "2") (pinfunction "2_2") (pintype "passive"))
      (node (ref "U4") (pin "8") (pinfunction "OUTR2_8") (pintype "passive"))
    )
    (net (code "124") (name "Net-(U4-OUTR3)") (class "Default")
      (node (ref "D36") (pin "2") (pinfunction "2_2") (pintype "passive"))
      (node (ref "U4") (pin "11") (pinfunction "OUTR3_11") (pintype "passive"))
    )
    (net (code "125") (name "Net-(U4-OUTR4)") (class "Default")
      (node (ref "D37") (pin "2") (pinfunction "2_2") (pintype "passive"))
      (node (ref "U4") (pin "14") (pinfunction "OUTR4_14") (pintype "passive"))
    )
    (net (code "126") (name "Net-(U4-OUTR5)") (class "Default")
      (node (ref "D38") (pin "2") (pinfunction "2_2") (pintype "passive"))
      (node (ref "U4") (pin "17") (pinfunction "OUTR5_17") (pintype "passive"))
    )
    (net (code "127") (name "Net-(U4-OUTR6)") (class "Default")
      (node (ref "D39") (pin "2") (pinfunction "2_2") (pintype "passive"))
      (node (ref "U4") (pin "20") (pinfunction "OUTR6_20") (pintype "passive"))
    )
    (net (code "128") (name "Net-(U4-OUTR7)") (class "Default")
      (node (ref "D40") (pin "2") (pinfunction "2_2") (pintype "passive"))
      (node (ref "U4") (pin "23") (pinfunction "OUTR7_23") (pintype "passive"))
    )
    (net (code "129") (name "Net-(U4-OUTR8)") (class "Default")
      (node (ref "D41") (pin "2") (pinfunction "2_2") (pintype "passive"))
      (node (ref "U4") (pin "30") (pinfunction "OUTR8_30") (pintype "passive"))
    )
    (net (code "130") (name "Net-(U4-OUTR12)") (class "Default")
      (node (ref "D45") (pin "2") (pinfunction "2_2") (pintype "passive"))
      (node (ref "U4") (pin "44") (pinfunction "OUTR12_44") (pintype "passive"))
    )
    (net (code "131") (name "Net-(U4-OUTR13)") (class "Default")
      (node (ref "D46") (pin "2") (pinfunction "2_2") (pintype "passive"))
      (node (ref "U4") (pin "47") (pinfunction "OUTR13_47") (pintype "passive"))
    )
    (net (code "132") (name "Net-(U4-OUTR14)") (class "Default")
      (node (ref "D47") (pin "2") (pinfunction "2_2") (pintype "passive"))
      (node (ref "U4") (pin "50") (pinfunction "OUTR14_50") (pintype "passive"))
    )
    (net (code "133") (name "Net-(U4-OUTR15)") (class "Default")
      (node (ref "D48") (pin "2") (pinfunction "2_2") (pintype "passive"))
      (node (ref "U4") (pin "53") (pinfunction "OUTR15_53") (pintype "passive"))
    )
    (net (code "134") (name "Net-(U5-OUTB0)") (class "Default")
      (node (ref "D49") (pin "4") (pinfunction "4_4") (pintype "passive"))
      (node (ref "U5") (pin "4") (pinfunction "OUTB0_4") (pintype "passive"))
    )
    (net (code "135") (name "Net-(U5-OUTB1)") (class "Default")
      (node (ref "D50") (pin "4") (pinfunction "4_4") (pintype "passive"))
      (node (ref "U5") (pin "7") (pinfunction "OUTB1_7") (pintype "passive"))
    )
    (net (code "136") (name "Net-(U5-OUTB2)") (class "Default")
      (node (ref "D51") (pin "4") (pinfunction "4_4") (pintype "passive"))
      (node (ref "U5") (pin "10") (pinfunction "OUTB2_10") (pintype "passive"))
    )
    (net (code "137") (name "Net-(U5-OUTB3)") (class "Default")
      (node (ref "D52") (pin "4") (pinfunction "4_4") (pintype "passive"))
      (node (ref "U5") (pin "13") (pinfunction "OUTB3_13") (pintype "passive"))
    )
    (net (code "138") (name "Net-(U5-OUTB4)") (class "Default")
      (node (ref "D53") (pin "4") (pinfunction "4_4") (pintype "passive"))
      (node (ref "U5") (pin "16") (pinfunction "OUTB4_16") (pintype "passive"))
    )
    (net (code "139") (name "Net-(U5-OUTB5)") (class "Default")
      (node (ref "D54") (pin "4") (pinfunction "4_4") (pintype "passive"))
      (node (ref "U5") (pin "19") (pinfunction "OUTB5_19") (pintype "passive"))
    )
    (net (code "140") (name "Net-(U5-OUTB6)") (class "Default")
      (node (ref "D55") (pin "4") (pinfunction "4_4") (pintype "passive"))
      (node (ref "U5") (pin "22") (pinfunction "OUTB6_22") (pintype "passive"))
    )
    (net (code "141") (name "Net-(U5-OUTB7)") (class "Default")
      (node (ref "D56") (pin "4") (pinfunction "4_4") (pintype "passive"))
      (node (ref "U5") (pin "25") (pinfunction "OUTB7_25") (pintype "passive"))
    )
    (net (code "142") (name "Net-(U5-OUTB8)") (class "Default")
      (node (ref "D57") (pin "4") (pinfunction "4_4") (pintype "passive"))
      (node (ref "U5") (pin "32") (pinfunction "OUTB8_32") (pintype "passive"))
    )
    (net (code "143") (name "Net-(U5-OUTB9)") (class "Default")
      (node (ref "D58") (pin "4") (pinfunction "4_4") (pintype "passive"))
      (node (ref "U5") (pin "35") (pinfunction "OUTB9_35") (pintype "passive"))
    )
    (net (code "144") (name "Net-(U5-OUTB10)") (class "Default")
      (node (ref "D59") (pin "4") (pinfunction "4_4") (pintype "passive"))
      (node (ref "U5") (pin "38") (pinfunction "OUTB10_38") (pintype "passive"))
    )
    (net (code "145") (name "Net-(U5-OUTG0)") (class "Default")
      (node (ref "D49") (pin "3") (pinfunction "3_3") (pintype "passive"))
      (node (ref "U5") (pin "3") (pinfunction "OUTG0_3") (pintype "passive"))
    )
    (net (code "146") (name "Net-(U5-OUTG1)") (class "Default")
      (node (ref "D50") (pin "3") (pinfunction "3_3") (pintype "passive"))
      (node (ref "U5") (pin "6") (pinfunction "OUTG1_6") (pintype "passive"))
    )
    (net (code "147") (name "Net-(U5-OUTG2)") (class "Default")
      (node (ref "D51") (pin "3") (pinfunction "3_3") (pintype "passive"))
      (node (ref "U5") (pin "9") (pinfunction "OUTG2_9") (pintype "passive"))
    )
    (net (code "148") (name "Net-(U5-OUTG3)") (class "Default")
      (node (ref "D52") (pin "3") (pinfunction "3_3") (pintype "passive"))
      (node (ref "U5") (pin "12") (pinfunction "OUTG3_12") (pintype "passive"))
    )
    (net (code "149") (name "Net-(U5-OUTG4)") (class "Default")
      (node (ref "D53") (pin "3") (pinfunction "3_3") (pintype "passive"))
      (node (ref "U5") (pin "15") (pinfunction "OUTG4_15") (pintype "passive"))
    )
    (net (code "150") (name "Net-(U5-OUTG5)") (class "Default")
      (node (ref "D54") (pin "3") (pinfunction "3_3") (pintype "passive"))
      (node (ref "U5") (pin "18") (pinfunction "OUTG5_18") (pintype "passive"))
    )
    (net (code "151") (name "Net-(U5-OUTG6)") (class "Default")
      (node (ref "D55") (pin "3") (pinfunction "3_3") (pintype "passive"))
      (node (ref "U5") (pin "21") (pinfunction "OUTG6_21") (pintype "passive"))
    )
    (net (code "152") (name "Net-(U5-OUTG7)") (class "Default")
      (node (ref "D56") (pin "3") (pinfunction "3_3") (pintype "passive"))
      (node (ref "U5") (pin "24") (pinfunction "OUTG7_24") (pintype "passive"))
    )
    (net (code "153") (name "Net-(U5-OUTG8)") (class "Default")
      (node (ref "D57") (pin "3") (pinfunction "3_3") (pintype "passive"))
      (node (ref "U5") (pin "31") (pinfunction "OUTG8_31") (pintype "passive"))
    )
    (net (code "154") (name "Net-(U5-OUTG9)") (class "Default")
      (node (ref "D58") (pin "3") (pinfunction "3_3") (pintype "passive"))
      (node (ref "U5") (pin "34") (pinfunction "OUTG9_34") (pintype "passive"))
    )
    (net (code "155") (name "Net-(U5-OUTG10)") (class "Default")
      (node (ref "D59") (pin "3") (pinfunction "3_3") (pintype "passive"))
      (node (ref "U5") (pin "37") (pinfunction "OUTG10_37") (pintype "passive"))
    )
    (net (code "156") (name "Net-(U5-OUTR0)") (class "Default")
      (node (ref "D49") (pin "2") (pinfunction "2_2") (pintype "passive"))
      (node (ref "U5") (pin "2") (pinfunction "OUTR0_2") (pintype "passive"))
    )
    (net (code "157") (name "Net-(U5-OUTR1)") (class "Default")
      (node (ref "D50") (pin "2") (pinfunction "2_2") (pintype "passive"))
      (node (ref "U5") (pin "5") (pinfunction "OUTR1_5") (pintype "passive"))
    )
    (net (code "158") (name "Net-(U5-OUTR2)") (class "Default")
      (node (ref "D51") (pin "2") (pinfunction "2_2") (pintype "passive"))
      (node (ref "U5") (pin "8") (pinfunction "OUTR2_8") (pintype "passive"))
    )
    (net (code "159") (name "Net-(U5-OUTR3)") (class "Default")
      (node (ref "D52") (pin "2") (pinfunction "2_2") (pintype "passive"))
      (node (ref "U5") (pin "11") (pinfunction "OUTR3_11") (pintype "passive"))
    )
    (net (code "160") (name "Net-(U5-OUTR4)") (class "Default")
      (node (ref "D53") (pin "2") (pinfunction "2_2") (pintype "passive"))
      (node (ref "U5") (pin "14") (pinfunction "OUTR4_14") (pintype "passive"))
    )
    (net (code "161") (name "Net-(U5-OUTR5)") (class "Default")
      (node (ref "D54") (pin "2") (pinfunction "2_2") (pintype "passive"))
      (node (ref "U5") (pin "17") (pinfunction "OUTR5_17") (pintype "passive"))
    )
    (net (code "162") (name "Net-(U5-OUTR6)") (class "Default")
      (node (ref "D55") (pin "2") (pinfunction "2_2") (pintype "passive"))
      (node (ref "U5") (pin "20") (pinfunction "OUTR6_20") (pintype "passive"))
    )
    (net (code "163") (name "Net-(U5-OUTR7)") (class "Default")
      (node (ref "D56") (pin "2") (pinfunction "2_2") (pintype "passive"))
      (node (ref "U5") (pin "23") (pinfunction "OUTR7_23") (pintype "passive"))
    )
    (net (code "164") (name "Net-(U5-OUTR8)") (class "Default")
      (node (ref "D57") (pin "2") (pinfunction "2_2") (pintype "passive"))
      (node (ref "U5") (pin "30") (pinfunction "OUTR8_30") (pintype "passive"))
    )
    (net (code "165") (name "Net-(U5-OUTR9)") (class "Default")
      (node (ref "D58") (pin "2") (pinfunction "2_2") (pintype "passive"))
      (node (ref "U5") (pin "33") (pinfunction "OUTR9_33") (pintype "passive"))
    )
    (net (code "166") (name "Net-(U5-OUTR10)") (class "Default")
      (node (ref "D59") (pin "2") (pinfunction "2_2") (pintype "passive"))
      (node (ref "U5") (pin "36") (pinfunction "OUTR10_36") (pintype "passive"))
    )
    (net (code "167") (name "Net-(U6-OUTB0)") (class "Default")
      (node (ref "D65") (pin "4") (pinfunction "4_4") (pintype "passive"))
      (node (ref "U6") (pin "4") (pinfunction "OUTB0_4") (pintype "passive"))
    )
    (net (code "168") (name "Net-(U6-OUTB1)") (class "Default")
      (node (ref "D66") (pin "4") (pinfunction "4_4") (pintype "passive"))
      (node (ref "U6") (pin "7") (pinfunction "OUTB1_7") (pintype "passive"))
    )
    (net (code "169") (name "Net-(U6-OUTB2)") (class "Default")
      (node (ref "D67") (pin "4") (pinfunction "4_4") (pintype "passive"))
      (node (ref "U6") (pin "10") (pinfunction "OUTB2_10") (pintype "passive"))
    )
    (net (code "170") (name "Net-(U6-OUTB3)") (class "Default")
      (node (ref "D68") (pin "4") (pinfunction "4_4") (pintype "passive"))
      (node (ref "U6") (pin "13") (pinfunction "OUTB3_13") (pintype "passive"))
    )
    (net (code "171") (name "Net-(U6-OUTB4)") (class "Default")
      (node (ref "D69") (pin "4") (pinfunction "4_4") (pintype "passive"))
      (node (ref "U6") (pin "16") (pinfunction "OUTB4_16") (pintype "passive"))
    )
    (net (code "172") (name "Net-(U6-OUTB5)") (class "Default")
      (node (ref "D70") (pin "4") (pinfunction "4_4") (pintype "passive"))
      (node (ref "U6") (pin "19") (pinfunction "OUTB5_19") (pintype "passive"))
    )
    (net (code "173") (name "Net-(U6-OUTB6)") (class "Default")
      (node (ref "D71") (pin "4") (pinfunction "4_4") (pintype "passive"))
      (node (ref "U6") (pin "22") (pinfunction "OUTB6_22") (pintype "passive"))
    )
    (net (code "174") (name "Net-(U6-OUTB7)") (class "Default")
      (node (ref "D72") (pin "4") (pinfunction "4_4") (pintype "passive"))
      (node (ref "U6") (pin "25") (pinfunction "OUTB7_25") (pintype "passive"))
    )
    (net (code "175") (name "Net-(U6-OUTB8)") (class "Default")
      (node (ref "D73") (pin "4") (pinfunction "4_4") (pintype "passive"))
      (node (ref "U6") (pin "32") (pinfunction "OUTB8_32") (pintype "passive"))
    )
    (net (code "176") (name "Net-(U6-OUTB9)") (class "Default")
      (node (ref "D74") (pin "4") (pinfunction "4_4") (pintype "passive"))
      (node (ref "U6") (pin "35") (pinfunction "OUTB9_35") (pintype "passive"))
    )
    (net (code "177") (name "Net-(U6-OUTB10)") (class "Default")
      (node (ref "D75") (pin "4") (pinfunction "4_4") (pintype "passive"))
      (node (ref "U6") (pin "38") (pinfunction "OUTB10_38") (pintype "passive"))
    )
    (net (code "178") (name "Net-(U6-OUTB11)") (class "Default")
      (node (ref "D76") (pin "4") (pinfunction "4_4") (pintype "passive"))
      (node (ref "U6") (pin "41") (pinfunction "OUTB11_41") (pintype "passive"))
    )
    (net (code "179") (name "Net-(U6-OUTB15)") (class "Default")
      (node (ref "D80") (pin "4") (pinfunction "4_4") (pintype "passive"))
      (node (ref "U6") (pin "55") (pinfunction "OUTB15_55") (pintype "passive"))
    )
    (net (code "180") (name "Net-(U6-OUTG0)") (class "Default")
      (node (ref "D65") (pin "3") (pinfunction "3_3") (pintype "passive"))
      (node (ref "U6") (pin "3") (pinfunction "OUTG0_3") (pintype "passive"))
    )
    (net (code "181") (name "Net-(U6-OUTG1)") (class "Default")
      (node (ref "D66") (pin "3") (pinfunction "3_3") (pintype "passive"))
      (node (ref "U6") (pin "6") (pinfunction "OUTG1_6") (pintype "passive"))
    )
    (net (code "182") (name "Net-(U6-OUTG2)") (class "Default")
      (node (ref "D67") (pin "3") (pinfunction "3_3") (pintype "passive"))
      (node (ref "U6") (pin "9") (pinfunction "OUTG2_9") (pintype "passive"))
    )
    (net (code "183") (name "Net-(U6-OUTG3)") (class "Default")
      (node (ref "D68") (pin "3") (pinfunction "3_3") (pintype "passive"))
      (node (ref "U6") (pin "12") (pinfunction "OUTG3_12") (pintype "passive"))
    )
    (net (code "184") (name "Net-(U6-OUTG4)") (class "Default")
      (node (ref "D69") (pin "3") (pinfunction "3_3") (pintype "passive"))
      (node (ref "U6") (pin "15") (pinfunction "OUTG4_15") (pintype "passive"))
    )
    (net (code "185") (name "Net-(U6-OUTG5)") (class "Default")
      (node (ref "D70") (pin "3") (pinfunction "3_3") (pintype "passive"))
      (node (ref "U6") (pin "18") (pinfunction "OUTG5_18") (pintype "passive"))
    )
    (net (code "186") (name "Net-(U6-OUTG6)") (class "Default")
      (node (ref "D71") (pin "3") (pinfunction "3_3") (pintype "passive"))
      (node (ref "U6") (pin "21") (pinfunction "OUTG6_21") (pintype "passive"))
    )
    (net (code "187") (name "Net-(U6-OUTG7)") (class "Default")
      (node (ref "D72") (pin "3") (pinfunction "3_3") (pintype "passive"))
      (node (ref "U6") (pin "24") (pinfunction "OUTG7_24") (pintype "passive"))
    )
    (net (code "188") (name "Net-(U6-OUTG8)") (class "Default")
      (node (ref "D73") (pin "3") (pinfunction "3_3") (pintype "passive"))
      (node (ref "U6") (pin "31") (pinfunction "OUTG8_31") (pintype "passive"))
    )
    (net (code "189") (name "Net-(U6-OUTG9)") (class "Default")
      (node (ref "D74") (pin "3") (pinfunction "3_3") (pintype "passive"))
      (node (ref "U6") (pin "34") (pinfunction "OUTG9_34") (pintype "passive"))
    )
    (net (code "190") (name "Net-(U6-OUTG10)") (class "Default")
      (node (ref "D75") (pin "3") (pinfunction "3_3") (pintype "passive"))
      (node (ref "U6") (pin "37") (pinfunction "OUTG10_37") (pintype "passive"))
    )
    (net (code "191") (name "Net-(U6-OUTG11)") (class "Default")
      (node (ref "D76") (pin "3") (pinfunction "3_3") (pintype "passive"))
      (node (ref "U6") (pin "40") (pinfunction "OUTG11_40") (pintype "passive"))
    )
    (net (code "192") (name "Net-(U6-OUTG15)") (class "Default")
      (node (ref "D80") (pin "3") (pinfunction "3_3") (pintype "passive"))
      (node (ref "U6") (pin "54") (pinfunction "OUTG15_54") (pintype "passive"))
    )
    (net (code "193") (name "Net-(U6-OUTR0)") (class "Default")
      (node (ref "D65") (pin "2") (pinfunction "2_2") (pintype "passive"))
      (node (ref "U6") (pin "2") (pinfunction "OUTR0_2") (pintype "passive"))
    )
    (net (code "194") (name "Net-(U6-OUTR1)") (class "Default")
      (node (ref "D66") (pin "2") (pinfunction "2_2") (pintype "passive"))
      (node (ref "U6") (pin "5") (pinfunction "OUTR1_5") (pintype "passive"))
    )
    (net (code "195") (name "Net-(U6-OUTR2)") (class "Default")
      (node (ref "D67") (pin "2") (pinfunction "2_2") (pintype "passive"))
      (node (ref "U6") (pin "8") (pinfunction "OUTR2_8") (pintype "passive"))
    )
    (net (code "196") (name "Net-(U6-OUTR3)") (class "Default")
      (node (ref "D68") (pin "2") (pinfunction "2_2") (pintype "passive"))
      (node (ref "U6") (pin "11") (pinfunction "OUTR3_11") (pintype "passive"))
    )
    (net (code "197") (name "Net-(U6-OUTR4)") (class "Default")
      (node (ref "D69") (pin "2") (pinfunction "2_2") (pintype "passive"))
      (node (ref "U6") (pin "14") (pinfunction "OUTR4_14") (pintype "passive"))
    )
    (net (code "198") (name "Net-(U6-OUTR5)") (class "Default")
      (node (ref "D70") (pin "2") (pinfunction "2_2") (pintype "passive"))
      (node (ref "U6") (pin "17") (pinfunction "OUTR5_17") (pintype "passive"))
    )
    (net (code "199") (name "Net-(U6-OUTR6)") (class "Default")
      (node (ref "D71") (pin "2") (pinfunction "2_2") (pintype "passive"))
      (node (ref "U6") (pin "20") (pinfunction "OUTR6_20") (pintype "passive"))
    )
    (net (code "200") (name "Net-(U6-OUTR7)") (class "Default")
      (node (ref "D72") (pin "2") (pinfunction "2_2") (pintype "passive"))
      (node (ref "U6") (pin "23") (pinfunction "OUTR7_23") (pintype "passive"))
    )
    (net (code "201") (name "Net-(U6-OUTR8)") (class "Default")
      (node (ref "D73") (pin "2") (pinfunction "2_2") (pintype "passive"))
      (node (ref "U6") (pin "30") (pinfunction "OUTR8_30") (pintype "passive"))
    )
    (net (code "202") (name "Net-(U6-OUTR9)") (class "Default")
      (node (ref "D74") (pin "2") (pinfunction "2_2") (pintype "passive"))
      (node (ref "U6") (pin "33") (pinfunction "OUTR9_33") (pintype "passive"))
    )
    (net (code "203") (name "Net-(U6-OUTR10)") (class "Default")
      (node (ref "D75") (pin "2") (pinfunction "2_2") (pintype "passive"))
      (node (ref "U6") (pin "36") (pinfunction "OUTR10_36") (pintype "passive"))
    )
    (net (code "204") (name "Net-(U6-OUTR11)") (class "Default")
      (node (ref "D76") (pin "2") (pinfunction "2_2") (pintype "passive"))
      (node (ref "U6") (pin "39") (pinfunction "OUTR11_39") (pintype "passive"))
    )
    (net (code "205") (name "Net-(U6-OUTR15)") (class "Default")
      (node (ref "D80") (pin "2") (pinfunction "2_2") (pintype "passive"))
      (node (ref "U6") (pin "53") (pinfunction "OUTR15_53") (pintype "passive"))
    )
    (net (code "206") (name "Net-(U7-OUTB0)") (class "Default")
      (node (ref "D81") (pin "4") (pinfunction "4_4") (pintype "passive"))
      (node (ref "U7") (pin "4") (pinfunction "OUTB0_4") (pintype "passive"))
    )
    (net (code "207") (name "Net-(U7-OUTB1)") (class "Default")
      (node (ref "D82") (pin "4") (pinfunction "4_4") (pintype "passive"))
      (node (ref "U7") (pin "7") (pinfunction "OUTB1_7") (pintype "passive"))
    )
    (net (code "208") (name "Net-(U7-OUTB2)") (class "Default")
      (node (ref "D83") (pin "4") (pinfunction "4_4") (pintype "passive"))
      (node (ref "U7") (pin "10") (pinfunction "OUTB2_10") (pintype "passive"))
    )
    (net (code "209") (name "Net-(U7-OUTB3)") (class "Default")
      (node (ref "D84") (pin "4") (pinfunction "4_4") (pintype "passive"))
      (node (ref "U7") (pin "13") (pinfunction "OUTB3_13") (pintype "passive"))
    )
    (net (code "210") (name "Net-(U7-OUTB4)") (class "Default")
      (node (ref "D85") (pin "4") (pinfunction "4_4") (pintype "passive"))
      (node (ref "U7") (pin "16") (pinfunction "OUTB4_16") (pintype "passive"))
    )
    (net (code "211") (name "Net-(U7-OUTB5)") (class "Default")
      (node (ref "D86") (pin "4") (pinfunction "4_4") (pintype "passive"))
      (node (ref "U7") (pin "19") (pinfunction "OUTB5_19") (pintype "passive"))
    )
    (net (code "212") (name "Net-(U7-OUTB6)") (class "Default")
      (node (ref "D87") (pin "4") (pinfunction "4_4") (pintype "passive"))
      (node (ref "U7") (pin "22") (pinfunction "OUTB6_22") (pintype "passive"))
    )
    (net (code "213") (name "Net-(U7-OUTB7)") (class "Default")
      (node (ref "D88") (pin "4") (pinfunction "4_4") (pintype "passive"))
      (node (ref "U7") (pin "25") (pinfunction "OUTB7_25") (pintype "passive"))
    )
    (net (code "214") (name "Net-(U7-OUTB8)") (class "Default")
      (node (ref "D89") (pin "4") (pinfunction "4_4") (pintype "passive"))
      (node (ref "U7") (pin "32") (pinfunction "OUTB8_32") (pintype "passive"))
    )
    (net (code "215") (name "Net-(U7-OUTB9)") (class "Default")
      (node (ref "D90") (pin "4") (pinfunction "4_4") (pintype "passive"))
      (node (ref "U7") (pin "35") (pinfunction "OUTB9_35") (pintype "passive"))
    )
    (net (code "216") (name "Net-(U7-OUTB10)") (class "Default")
      (node (ref "D91") (pin "4") (pinfunction "4_4") (pintype "passive"))
      (node (ref "U7") (pin "38") (pinfunction "OUTB10_38") (pintype "passive"))
    )
    (net (code "217") (name "Net-(U7-OUTB11)") (class "Default")
      (node (ref "D92") (pin "4") (pinfunction "4_4") (pintype "passive"))
      (node (ref "U7") (pin "41") (pinfunction "OUTB11_41") (pintype "passive"))
    )
    (net (code "218") (name "Net-(U7-OUTB12)") (class "Default")
      (node (ref "D93") (pin "4") (pinfunction "4_4") (pintype "passive"))
      (node (ref "U7") (pin "46") (pinfunction "OUTB12_46") (pintype "passive"))
    )
    (net (code "219") (name "Net-(U7-OUTB13)") (class "Default")
      (node (ref "D94") (pin "4") (pinfunction "4_4") (pintype "passive"))
      (node (ref "U7") (pin "49") (pinfunction "OUTB13_49") (pintype "passive"))
    )
    (net (code "220") (name "Net-(U7-OUTB14)") (class "Default")
      (node (ref "D95") (pin "4") (pinfunction "4_4") (pintype "passive"))
      (node (ref "U7") (pin "52") (pinfunction "OUTB14_52") (pintype "passive"))
    )
    (net (code "221") (name "Net-(U7-OUTG0)") (class "Default")
      (node (ref "D81") (pin "3") (pinfunction "3_3") (pintype "passive"))
      (node (ref "U7") (pin "3") (pinfunction "OUTG0_3") (pintype "passive"))
    )
    (net (code "222") (name "Net-(U7-OUTG1)") (class "Default")
      (node (ref "D82") (pin "3") (pinfunction "3_3") (pintype "passive"))
      (node (ref "U7") (pin "6") (pinfunction "OUTG1_6") (pintype "passive"))
    )
    (net (code "223") (name "Net-(U7-OUTG2)") (class "Default")
      (node (ref "D83") (pin "3") (pinfunction "3_3") (pintype "passive"))
      (node (ref "U7") (pin "9") (pinfunction "OUTG2_9") (pintype "passive"))
    )
    (net (code "224") (name "Net-(U7-OUTG3)") (class "Default")
      (node (ref "D84") (pin "3") (pinfunction "3_3") (pintype "passive"))
      (node (ref "U7") (pin "12") (pinfunction "OUTG3_12") (pintype "passive"))
    )
    (net (code "225") (name "Net-(U7-OUTG4)") (class "Default")
      (node (ref "D85") (pin "3") (pinfunction "3_3") (pintype "passive"))
      (node (ref "U7") (pin "15") (pinfunction "OUTG4_15") (pintype "passive"))
    )
    (net (code "226") (name "Net-(U7-OUTG5)") (class "Default")
      (node (ref "D86") (pin "3") (pinfunction "3_3") (pintype "passive"))
      (node (ref "U7") (pin "18") (pinfunction "OUTG5_18") (pintype "passive"))
    )
    (net (code "227") (name "Net-(U7-OUTG6)") (class "Default")
      (node (ref "D87") (pin "3") (pinfunction "3_3") (pintype "passive"))
      (node (ref "U7") (pin "21") (pinfunction "OUTG6_21") (pintype "passive"))
    )
    (net (code "228") (name "Net-(U7-OUTG7)") (class "Default")
      (node (ref "D88") (pin "3") (pinfunction "3_3") (pintype "passive"))
      (node (ref "U7") (pin "24") (pinfunction "OUTG7_24") (pintype "passive"))
    )
    (net (code "229") (name "Net-(U7-OUTG8)") (class "Default")
      (node (ref "D89") (pin "3") (pinfunction "3_3") (pintype "passive"))
      (node (ref "U7") (pin "31") (pinfunction "OUTG8_31") (pintype "passive"))
    )
    (net (code "230") (name "Net-(U7-OUTG9)") (class "Default")
      (node (ref "D90") (pin "3") (pinfunction "3_3") (pintype "passive"))
      (node (ref "U7") (pin "34") (pinfunction "OUTG9_34") (pintype "passive"))
    )
    (net (code "231") (name "Net-(U7-OUTG10)") (class "Default")
      (node (ref "D91") (pin "3") (pinfunction "3_3") (pintype "passive"))
      (node (ref "U7") (pin "37") (pinfunction "OUTG10_37") (pintype "passive"))
    )
    (net (code "232") (name "Net-(U7-OUTG11)") (class "Default")
      (node (ref "D92") (pin "3") (pinfunction "3_3") (pintype "passive"))
      (node (ref "U7") (pin "40") (pinfunction "OUTG11_40") (pintype "passive"))
    )
    (net (code "233") (name "Net-(U7-OUTG12)") (class "Default")
      (node (ref "D93") (pin "3") (pinfunction "3_3") (pintype "passive"))
      (node (ref "U7") (pin "45") (pinfunction "OUTG12_45") (pintype "passive"))
    )
    (net (code "234") (name "Net-(U7-OUTG13)") (class "Default")
      (node (ref "D94") (pin "3") (pinfunction "3_3") (pintype "passive"))
      (node (ref "U7") (pin "48") (pinfunction "OUTG13_48") (pintype "passive"))
    )
    (net (code "235") (name "Net-(U7-OUTG14)") (class "Default")
      (node (ref "D95") (pin "3") (pinfunction "3_3") (pintype "passive"))
      (node (ref "U7") (pin "51") (pinfunction "OUTG14_51") (pintype "passive"))
    )
    (net (code "236") (name "Net-(U7-OUTR0)") (class "Default")
      (node (ref "D81") (pin "2") (pinfunction "2_2") (pintype "passive"))
      (node (ref "U7") (pin "2") (pinfunction "OUTR0_2") (pintype "passive"))
    )
    (net (code "237") (name "Net-(U7-OUTR1)") (class "Default")
      (node (ref "D82") (pin "2") (pinfunction "2_2") (pintype "passive"))
      (node (ref "U7") (pin "5") (pinfunction "OUTR1_5") (pintype "passive"))
    )
    (net (code "238") (name "Net-(U7-OUTR2)") (class "Default")
      (node (ref "D83") (pin "2") (pinfunction "2_2") (pintype "passive"))
      (node (ref "U7") (pin "8") (pinfunction "OUTR2_8") (pintype "passive"))
    )
    (net (code "239") (name "Net-(U7-OUTR3)") (class "Default")
      (node (ref "D84") (pin "2") (pinfunction "2_2") (pintype "passive"))
      (node (ref "U7") (pin "11") (pinfunction "OUTR3_11") (pintype "passive"))
    )
    (net (code "240") (name "Net-(U7-OUTR4)") (class "Default")
      (node (ref "D85") (pin "2") (pinfunction "2_2") (pintype "passive"))
      (node (ref "U7") (pin "14") (pinfunction "OUTR4_14") (pintype "passive"))
    )
    (net (code "241") (name "Net-(U7-OUTR5)") (class "Default")
      (node (ref "D86") (pin "2") (pinfunction "2_2") (pintype "passive"))
      (node (ref "U7") (pin "17") (pinfunction "OUTR5_17") (pintype "passive"))
    )
    (net (code "242") (name "Net-(U7-OUTR6)") (class "Default")
      (node (ref "D87") (pin "2") (pinfunction "2_2") (pintype "passive"))
      (node (ref "U7") (pin "20") (pinfunction "OUTR6_20") (pintype "passive"))
    )
    (net (code "243") (name "Net-(U7-OUTR7)") (class "Default")
      (node (ref "D88") (pin "2") (pinfunction "2_2") (pintype "passive"))
      (node (ref "U7") (pin "23") (pinfunction "OUTR7_23") (pintype "passive"))
    )
    (net (code "244") (name "Net-(U7-OUTR8)") (class "Default")
      (node (ref "D89") (pin "2") (pinfunction "2_2") (pintype "passive"))
      (node (ref "U7") (pin "30") (pinfunction "OUTR8_30") (pintype "passive"))
    )
    (net (code "245") (name "Net-(U7-OUTR9)") (class "Default")
      (node (ref "D90") (pin "2") (pinfunction "2_2") (pintype "passive"))
      (node (ref "U7") (pin "33") (pinfunction "OUTR9_33") (pintype "passive"))
    )
    (net (code "246") (name "Net-(U7-OUTR10)") (class "Default")
      (node (ref "D91") (pin "2") (pinfunction "2_2") (pintype "passive"))
      (node (ref "U7") (pin "36") (pinfunction "OUTR10_36") (pintype "passive"))
    )
    (net (code "247") (name "Net-(U7-OUTR11)") (class "Default")
      (node (ref "D92") (pin "2") (pinfunction "2_2") (pintype "passive"))
      (node (ref "U7") (pin "39") (pinfunction "OUTR11_39") (pintype "passive"))
    )
    (net (code "248") (name "Net-(U7-OUTR12)") (class "Default")
      (node (ref "D93") (pin "2") (pinfunction "2_2") (pintype "passive"))
      (node (ref "U7") (pin "44") (pinfunction "OUTR12_44") (pintype "passive"))
    )
    (net (code "249") (name "Net-(U7-OUTR13)") (class "Default")
      (node (ref "D94") (pin "2") (pinfunction "2_2") (pintype "passive"))
      (node (ref "U7") (pin "47") (pinfunction "OUTR13_47") (pintype "passive"))
    )
    (net (code "250") (name "Net-(U7-OUTR14)") (class "Default")
      (node (ref "D95") (pin "2") (pinfunction "2_2") (pintype "passive"))
      (node (ref "U7") (pin "50") (pinfunction "OUTR14_50") (pintype "passive"))
    )
    (net (code "251") (name "VCC_P3V3") (class "Default")
      (node (ref "C1") (pin "2") (pinfunction "2_2") (pintype "passive"))
      (node (ref "C2") (pin "2") (pinfunction "2_2") (pintype "passive"))
      (node (ref "C3") (pin "2") (pinfunction "2_2") (pintype "passive"))
      (node (ref "C4") (pin "2") (pinfunction "2_2") (pintype "passive"))
      (node (ref "C5") (pin "2") (pinfunction "2_2") (pintype "passive"))
      (node (ref "C6") (pin "2") (pinfunction "2_2") (pintype "passive"))
      (node (ref "D1") (pin "1") (pinfunction "1_1") (pintype "passive"))
      (node (ref "D10") (pin "1") (pinfunction "1_1") (pintype "passive"))
      (node (ref "D11") (pin "1") (pinfunction "1_1") (pintype "passive"))
      (node (ref "D12") (pin "1") (pinfunction "1_1") (pintype "passive"))
      (node (ref "D13") (pin "1") (pinfunction "1_1") (pintype "passive"))
      (node (ref "D14") (pin "1") (pinfunction "1_1") (pintype "passive"))
      (node (ref "D15") (pin "1") (pinfunction "1_1") (pintype "passive"))
      (node (ref "D16") (pin "1") (pinfunction "1_1") (pintype "passive"))
      (node (ref "D17") (pin "1") (pinfunction "1_1") (pintype "passive"))
      (node (ref "D18") (pin "1") (pinfunction "1_1") (pintype "passive"))
      (node (ref "D19") (pin "1") (pinfunction "1_1") (pintype "passive"))
      (node (ref "D2") (pin "1") (pinfunction "1_1") (pintype "passive"))
      (node (ref "D20") (pin "1") (pinfunction "1_1") (pintype "passive"))
      (node (ref "D21") (pin "1") (pinfunction "1_1") (pintype "passive"))
      (node (ref "D22") (pin "1") (pinfunction "1_1") (pintype "passive"))
      (node (ref "D23") (pin "1") (pinfunction "1_1") (pintype "passive"))
      (node (ref "D25") (pin "1") (pinfunction "1_1") (pintype "passive"))
      (node (ref "D26") (pin "1") (pinfunction "1_1") (pintype "passive"))
      (node (ref "D27") (pin "1") (pinfunction "1_1") (pintype "passive"))
      (node (ref "D28") (pin "1") (pinfunction "1_1") (pintype "passive"))
      (node (ref "D29") (pin "1") (pinfunction "1_1") (pintype "passive"))
      (node (ref "D3") (pin "1") (pinfunction "1_1") (pintype "passive"))
      (node (ref "D30") (pin "1") (pinfunction "1_1") (pintype "passive"))
      (node (ref "D31") (pin "1") (pinfunction "1_1") (pintype "passive"))
      (node (ref "D32") (pin "1") (pinfunction "1_1") (pintype "passive"))
      (node (ref "D33") (pin "1") (pinfunction "1_1") (pintype "passive"))
      (node (ref "D34") (pin "1") (pinfunction "1_1") (pintype "passive"))
      (node (ref "D35") (pin "1") (pinfunction "1_1") (pintype "passive"))
      (node (ref "D36") (pin "1") (pinfunction "1_1") (pintype "passive"))
      (node (ref "D37") (pin "1") (pinfunction "1_1") (pintype "passive"))
      (node (ref "D38") (pin "1") (pinfunction "1_1") (pintype "passive"))
      (node (ref "D39") (pin "1") (pinfunction "1_1") (pintype "passive"))
      (node (ref "D4") (pin "1") (pinfunction "1_1") (pintype "passive"))
      (node (ref "D40") (pin "1") (pinfunction "1_1") (pintype "passive"))
      (node (ref "D41") (pin "1") (pinfunction "1_1") (pintype "passive"))
      (node (ref "D45") (pin "1") (pinfunction "1_1") (pintype "passive"))
      (node (ref "D46") (pin "1") (pinfunction "1_1") (pintype "passive"))
      (node (ref "D47") (pin "1") (pinfunction "1_1") (pintype "passive"))
      (node (ref "D48") (pin "1") (pinfunction "1_1") (pintype "passive"))
      (node (ref "D49") (pin "1") (pinfunction "1_1") (pintype "passive"))
      (node (ref "D5") (pin "1") (pinfunction "1_1") (pintype "passive"))
      (node (ref "D50") (pin "1") (pinfunction "1_1") (pintype "passive"))
      (node (ref "D51") (pin "1") (pinfunction "1_1") (pintype "passive"))
      (node (ref "D52") (pin "1") (pinfunction "1_1") (pintype "passive"))
      (node (ref "D53") (pin "1") (pinfunction "1_1") (pintype "passive"))
      (node (ref "D54") (pin "1") (pinfunction "1_1") (pintype "passive"))
      (node (ref "D55") (pin "1") (pinfunction "1_1") (pintype "passive"))
      (node (ref "D56") (pin "1") (pinfunction "1_1") (pintype "passive"))
      (node (ref "D57") (pin "1") (pinfunction "1_1") (pintype "passive"))
      (node (ref "D58") (pin "1") (pinfunction "1_1") (pintype "passive"))
      (node (ref "D59") (pin "1") (pinfunction "1_1") (pintype "passive"))
      (node (ref "D6") (pin "1") (pinfunction "1_1") (pintype "passive"))
      (node (ref "D65") (pin "1") (pinfunction "1_1") (pintype "passive"))
      (node (ref "D66") (pin "1") (pinfunction "1_1") (pintype "passive"))
      (node (ref "D67") (pin "1") (pinfunction "1_1") (pintype "passive"))
      (node (ref "D68") (pin "1") (pinfunction "1_1") (pintype "passive"))
      (node (ref "D69") (pin "1") (pinfunction "1_1") (pintype "passive"))
      (node (ref "D7") (pin "1") (pinfunction "1_1") (pintype "passive"))
      (node (ref "D70") (pin "1") (pinfunction "1_1") (pintype "passive"))
      (node (ref "D71") (pin "1") (pinfunction "1_1") (pintype "passive"))
      (node (ref "D72") (pin "1") (pinfunction "1_1") (pintype "passive"))
      (node (ref "D73") (pin "1") (pinfunction "1_1") (pintype "passive"))
      (node (ref "D74") (pin "1") (pinfunction "1_1") (pintype "passive"))
      (node (ref "D75") (pin "1") (pinfunction "1_1") (pintype "passive"))
      (node (ref "D76") (pin "1") (pinfunction "1_1") (pintype "passive"))
      (node (ref "D8") (pin "1") (pinfunction "1_1") (pintype "passive"))
      (node (ref "D80") (pin "1") (pinfunction "1_1") (pintype "passive"))
      (node (ref "D81") (pin "1") (pinfunction "1_1") (pintype "passive"))
      (node (ref "D82") (pin "1") (pinfunction "1_1") (pintype "passive"))
      (node (ref "D83") (pin "1") (pinfunction "1_1") (pintype "passive"))
      (node (ref "D84") (pin "1") (pinfunction "1_1") (pintype "passive"))
      (node (ref "D85") (pin "1") (pinfunction "1_1") (pintype "passive"))
      (node (ref "D86") (pin "1") (pinfunction "1_1") (pintype "passive"))
      (node (ref "D87") (pin "1") (pinfunction "1_1") (pintype "passive"))
      (node (ref "D88") (pin "1") (pinfunction "1_1") (pintype "passive"))
      (node (ref "D89") (pin "1") (pinfunction "1_1") (pintype "passive"))
      (node (ref "D9") (pin "1") (pinfunction "1_1") (pintype "passive"))
      (node (ref "D90") (pin "1") (pinfunction "1_1") (pintype "passive"))
      (node (ref "D91") (pin "1") (pinfunction "1_1") (pintype "passive"))
      (node (ref "D92") (pin "1") (pinfunction "1_1") (pintype "passive"))
      (node (ref "D93") (pin "1") (pinfunction "1_1") (pintype "passive"))
      (node (ref "D94") (pin "1") (pinfunction "1_1") (pintype "passive"))
      (node (ref "D95") (pin "1") (pinfunction "1_1") (pintype "passive"))
      (node (ref "U2") (pin "43") (pinfunction "VCC_43") (pintype "passive"))
      (node (ref "U3") (pin "43") (pinfunction "VCC_43") (pintype "passive"))
      (node (ref "U4") (pin "43") (pinfunction "VCC_43") (pintype "passive"))
      (node (ref "U5") (pin "43") (pinfunction "VCC_43") (pintype "passive"))
      (node (ref "U6") (pin "43") (pinfunction "VCC_43") (pintype "passive"))
      (node (ref "U7") (pin "43") (pinfunction "VCC_43") (pintype "passive"))
    )
    (net (code "252") (name "unconnected-(J1-GND-Pad2)") (class "Default")
      (node (ref "J1") (pin "2") (pinfunction "GND_2") (pintype "passive"))
    )
    (net (code "253") (name "unconnected-(J1-GND-Pad10)") (class "Default")
      (node (ref "J1") (pin "10") (pinfunction "GND_10") (pintype "passive"))
    )
    (net (code "254") (name "unconnected-(J1-NC-Pad7)") (class "Default")
      (node (ref "J1") (pin "7") (pinfunction "NC_7") (pintype "passive"))
    )
    (net (code "255") (name "unconnected-(J1-NC-Pad8)") (class "Default")
      (node (ref "J1") (pin "8") (pinfunction "NC_8") (pintype "passive"))
    )
    (net (code "256") (name "unconnected-(J1-TCK-Pad1)") (class "Default")
      (node (ref "J1") (pin "1") (pinfunction "TCK_1") (pintype "passive"))
    )
    (net (code "257") (name "unconnected-(J1-TDI-Pad9)") (class "Default")
      (node (ref "J1") (pin "9") (pinfunction "TDI_9") (pintype "passive"))
    )
    (net (code "258") (name "unconnected-(J1-TDO-Pad3)") (class "Default")
      (node (ref "J1") (pin "3") (pinfunction "TDO_3") (pintype "passive"))
    )
    (net (code "259") (name "unconnected-(J1-TMS-Pad5)") (class "Default")
      (node (ref "J1") (pin "5") (pinfunction "TMS_5") (pintype "passive"))
    )
    (net (code "260") (name "unconnected-(J1-VTG-Pad4)") (class "Default")
      (node (ref "J1") (pin "4") (pinfunction "VTG_4") (pintype "passive"))
    )
    (net (code "261") (name "unconnected-(J1-~{RST}-Pad6)") (class "Default")
      (node (ref "J1") (pin "6") (pinfunction "~{RST}_6") (pintype "passive"))
    )
    (net (code "262") (name "unconnected-(U1-AVCC-Pad39)") (class "Default")
      (node (ref "U1") (pin "39") (pinfunction "AVCC_39") (pintype "power_in"))
    )
    (net (code "263") (name "unconnected-(U1-GND-Pad8)") (class "Default")
      (node (ref "U1") (pin "8") (pinfunction "GND_8") (pintype "power_in"))
    )
    (net (code "264") (name "unconnected-(U1-GND-Pad18)") (class "Default")
      (node (ref "U1") (pin "18") (pinfunction "GND_18") (pintype "power_in"))
    )
    (net (code "265") (name "unconnected-(U1-GND-Pad30)") (class "Default")
      (node (ref "U1") (pin "30") (pinfunction "GND_30") (pintype "power_in"))
    )
    (net (code "266") (name "unconnected-(U1-GND-Pad38)") (class "Default")
      (node (ref "U1") (pin "38") (pinfunction "GND_38") (pintype "power_in"))
    )
    (net (code "267") (name "unconnected-(U1-PA0{slash}SYNC{slash}ADC0{slash}AC0{slash}AREF-Pad40)") (class "Default")
      (node (ref "U1") (pin "40") (pinfunction "PA0/SYNC/ADC0/AC0/AREF_40") (pintype "bidirectional"))
    )
    (net (code "268") (name "unconnected-(U1-PA1{slash}SYNC{slash}ADC1{slash}AC1-Pad41)") (class "Default")
      (node (ref "U1") (pin "41") (pinfunction "PA1/SYNC/ADC1/AC1_41") (pintype "bidirectional"))
    )
    (net (code "269") (name "unconnected-(U1-PA2{slash}SYNC{slash}ASYNC{slash}ADC2{slash}AC2-Pad42)") (class "Default")
      (node (ref "U1") (pin "42") (pinfunction "PA2/SYNC/ASYNC/ADC2/AC2_42") (pintype "bidirectional"))
    )
    (net (code "270") (name "unconnected-(U1-PA3{slash}SYNC{slash}ADC3{slash}AC3-Pad43)") (class "Default")
      (node (ref "U1") (pin "43") (pinfunction "PA3/SYNC/ADC3/AC3_43") (pintype "bidirectional"))
    )
    (net (code "271") (name "unconnected-(U1-PA4{slash}SYNC{slash}ADC4{slash}AC4-Pad44)") (class "Default")
      (node (ref "U1") (pin "44") (pinfunction "PA4/SYNC/ADC4/AC4_44") (pintype "bidirectional"))
    )
    (net (code "272") (name "unconnected-(U1-PA5{slash}SYNC{slash}ADC5{slash}AC5-Pad1)") (class "Default")
      (node (ref "U1") (pin "1") (pinfunction "PA5/SYNC/ADC5/AC5_1") (pintype "bidirectional"))
    )
    (net (code "273") (name "unconnected-(U1-PA6{slash}SYNC{slash}ADC6{slash}AC6{slash}AC1OUT-Pad2)") (class "Default")
      (node (ref "U1") (pin "2") (pinfunction "PA6/SYNC/ADC6/AC6/AC1OUT_2") (pintype "bidirectional"))
    )
    (net (code "274") (name "unconnected-(U1-PA7{slash}SYNC{slash}ADC7{slash}AC7{slash}AC0OUT-Pad3)") (class "Default")
      (node (ref "U1") (pin "3") (pinfunction "PA7/SYNC/ADC7/AC7/AC0OUT_3") (pintype "bidirectional"))
    )
    (net (code "275") (name "unconnected-(U1-PB0{slash}SYNC{slash}ADC8{slash}AREF-Pad4)") (class "Default")
      (node (ref "U1") (pin "4") (pinfunction "PB0/SYNC/ADC8/AREF_4") (pintype "bidirectional"))
    )
    (net (code "276") (name "unconnected-(U1-PB1{slash}SYNC{slash}ADC9-Pad5)") (class "Default")
      (node (ref "U1") (pin "5") (pinfunction "PB1/SYNC/ADC9_5") (pintype "bidirectional"))
    )
    (net (code "277") (name "unconnected-(U1-PB2{slash}SYNC{slash}ASYNC{slash}ADC10{slash}DAC0-Pad6)") (class "Default")
      (node (ref "U1") (pin "6") (pinfunction "PB2/SYNC/ASYNC/ADC10/DAC0_6") (pintype "bidirectional"))
    )
    (net (code "278") (name "unconnected-(U1-PB3{slash}SYNC{slash}ADC11{slash}DAC1-Pad7)") (class "Default")
      (node (ref "U1") (pin "7") (pinfunction "PB3/SYNC/ADC11/DAC1_7") (pintype "bidirectional"))
    )
    (net (code "279") (name "unconnected-(U1-PC0{slash}SYNC{slash}OC0A{slash}~{OC0ALS}{slash}SDA{slash}SDAIN-Pad10)") (class "Default")
      (node (ref "U1") (pin "10") (pinfunction "PC0/SYNC/OC0A/~{OC0ALS}/SDA/SDAIN_10") (pintype "bidirectional"))
    )
    (net (code "280") (name "unconnected-(U1-PC1{slash}SYNC{slash}OC0B{slash}OC0AHS{slash}XCK0{slash}SCL{slash}SCLIN-Pad11)") (class "Default")
      (node (ref "U1") (pin "11") (pinfunction "PC1/SYNC/OC0B/OC0AHS/XCK0/SCL/SCLIN_11") (pintype "bidirectional"))
    )
    (net (code "281") (name "unconnected-(U1-PC2{slash}SYNC{slash}ASYNC{slash}OC0C{slash}~{OC0BLS}{slash}RXD0{slash}SDAOUT-Pad12)") (class "Default")
      (node (ref "U1") (pin "12") (pinfunction "PC2/SYNC/ASYNC/OC0C/~{OC0BLS}/RXD0/SDAOUT_12") (pintype "bidirectional"))
    )
    (net (code "282") (name "unconnected-(U1-PC3{slash}SYNC{slash}OC0D{slash}OC0BHS{slash}TXD0{slash}SCLOUT-Pad13)") (class "Default")
      (node (ref "U1") (pin "13") (pinfunction "PC3/SYNC/OC0D/OC0BHS/TXD0/SCLOUT_13") (pintype "bidirectional"))
    )
    (net (code "283") (name "unconnected-(U1-PC4{slash}SYNC{slash}~{OC0CLS}{slash}OC1A{slash}~{SS}-Pad14)") (class "Default")
      (node (ref "U1") (pin "14") (pinfunction "PC4/SYNC/~{OC0CLS}/OC1A/~{SS}_14") (pintype "bidirectional"))
    )
    (net (code "284") (name "unconnected-(U1-PC5{slash}SYNC{slash}OC0CHS{slash}OC1B{slash}XCK1{slash}MOSI-Pad15)") (class "Default")
      (node (ref "U1") (pin "15") (pinfunction "PC5/SYNC/OC0CHS/OC1B/XCK1/MOSI_15") (pintype "bidirectional"))
    )
    (net (code "285") (name "unconnected-(U1-PC6{slash}SYNC{slash}~{OC0DLS}{slash}RXD1{slash}MISO{slash}CLKRTC-Pad16)") (class "Default")
      (node (ref "U1") (pin "16") (pinfunction "PC6/SYNC/~{OC0DLS}/RXD1/MISO/CLKRTC_16") (pintype "bidirectional"))
    )
    (net (code "286") (name "unconnected-(U1-PC7{slash}SYNC{slash}OC0DHS{slash}TXD1{slash}SCK{slash}CLKPER{slash}EVOUT-Pad17)") (class "Default")
      (node (ref "U1") (pin "17") (pinfunction "PC7/SYNC/OC0DHS/TXD1/SCK/CLKPER/EVOUT_17") (pintype "bidirectional"))
    )
    (net (code "287") (name "unconnected-(U1-PD0{slash}SYNC{slash}OC0A-Pad20)") (class "Default")
      (node (ref "U1") (pin "20") (pinfunction "PD0/SYNC/OC0A_20") (pintype "bidirectional"))
    )
    (net (code "288") (name "unconnected-(U1-PD1{slash}SYNC{slash}OC0B{slash}XCK0-Pad21)") (class "Default")
      (node (ref "U1") (pin "21") (pinfunction "PD1/SYNC/OC0B/XCK0_21") (pintype "bidirectional"))
    )
    (net (code "289") (name "unconnected-(U1-PD2{slash}SYNC{slash}ASYNC{slash}OC0C{slash}RXD0-Pad22)") (class "Default")
      (node (ref "U1") (pin "22") (pinfunction "PD2/SYNC/ASYNC/OC0C/RXD0_22") (pintype "bidirectional"))
    )
    (net (code "290") (name "unconnected-(U1-PD3{slash}SYNC{slash}OC0D{slash}TXD0-Pad23)") (class "Default")
      (node (ref "U1") (pin "23") (pinfunction "PD3/SYNC/OC0D/TXD0_23") (pintype "bidirectional"))
    )
    (net (code "291") (name "unconnected-(U1-PD4{slash}SYNC{slash}OC1A{slash}~{SS}-Pad24)") (class "Default")
      (node (ref "U1") (pin "24") (pinfunction "PD4/SYNC/OC1A/~{SS}_24") (pintype "bidirectional"))
    )
    (net (code "292") (name "unconnected-(U1-PD5{slash}SYNC{slash}OC1B{slash}XCK1{slash}MOSI-Pad25)") (class "Default")
      (node (ref "U1") (pin "25") (pinfunction "PD5/SYNC/OC1B/XCK1/MOSI_25") (pintype "bidirectional"))
    )
    (net (code "293") (name "unconnected-(U1-PD6{slash}SYNC{slash}D-{slash}RXD1{slash}MISO-Pad26)") (class "Default")
      (node (ref "U1") (pin "26") (pinfunction "PD6/SYNC/D-/RXD1/MISO_26") (pintype "bidirectional"))
    )
    (net (code "294") (name "unconnected-(U1-PD7{slash}SYNC{slash}D+{slash}TXD1{slash}SCK{slash}CLKPER{slash}EVOUT-Pad27)") (class "Default")
      (node (ref "U1") (pin "27") (pinfunction "PD7/SYNC/D+/TXD1/SCK/CLKPER/EVOUT_27") (pintype "bidirectional"))
    )
    (net (code "295") (name "unconnected-(U1-PDI{slash}PDI_DATA-Pad34)") (class "Default")
      (node (ref "U1") (pin "34") (pinfunction "PDI/PDI_DATA_34") (pintype "bidirectional"))
    )
    (net (code "296") (name "unconnected-(U1-PE0{slash}SYNC{slash}OC0A{slash}SDA-Pad28)") (class "Default")
      (node (ref "U1") (pin "28") (pinfunction "PE0/SYNC/OC0A/SDA_28") (pintype "bidirectional"))
    )
    (net (code "297") (name "unconnected-(U1-PE1{slash}SYNC{slash}OC0B{slash}XCK0{slash}SCL-Pad29)") (class "Default")
      (node (ref "U1") (pin "29") (pinfunction "PE1/SYNC/OC0B/XCK0/SCL_29") (pintype "bidirectional"))
    )
    (net (code "298") (name "unconnected-(U1-PE2{slash}SYNC{slash}ASYNC{slash}OC0C{slash}RXD0-Pad32)") (class "Default")
      (node (ref "U1") (pin "32") (pinfunction "PE2/SYNC/ASYNC/OC0C/RXD0_32") (pintype "bidirectional"))
    )
    (net (code "299") (name "unconnected-(U1-PE3{slash}SYNC{slash}OC0D{slash}TXD0-Pad33)") (class "Default")
      (node (ref "U1") (pin "33") (pinfunction "PE3/SYNC/OC0D/TXD0_33") (pintype "bidirectional"))
    )
    (net (code "300") (name "unconnected-(U1-PR0{slash}SYNC{slash}XTAL2{slash}TOSC2-Pad36)") (class "Default")
      (node (ref "U1") (pin "36") (pinfunction "PR0/SYNC/XTAL2/TOSC2_36") (pintype "bidirectional"))
    )
    (net (code "301") (name "unconnected-(U1-PR1{slash}SYNC{slash}XTAL1{slash}TOSC1-Pad37)") (class "Default")
      (node (ref "U1") (pin "37") (pinfunction "PR1/SYNC/XTAL1/TOSC1_37") (pintype "bidirectional"))
    )
    (net (code "302") (name "unconnected-(U1-VCC-Pad9)") (class "Default")
      (node (ref "U1") (pin "9") (pinfunction "VCC_9") (pintype "power_in"))
    )
    (net (code "303") (name "unconnected-(U1-VCC-Pad19)") (class "Default")
      (node (ref "U1") (pin "19") (pinfunction "VCC_19") (pintype "power_in"))
    )
    (net (code "304") (name "unconnected-(U1-VCC-Pad31)") (class "Default")
      (node (ref "U1") (pin "31") (pinfunction "VCC_31") (pintype "power_in"))
    )
    (net (code "305") (name "unconnected-(U1-~{RESET}{slash}PDI_CLOCK-Pad35)") (class "Default")
      (node (ref "U1") (pin "35") (pinfunction "~{RESET}/PDI_CLOCK_35") (pintype "input"))
    )
    (net (code "306") (name "unconnected-(U2-BLANK-Pad29)") (class "Default")
      (node (ref "U2") (pin "29") (pinfunction "BLANK_29") (pintype "passive"))
    )
    (net (code "307") (name "unconnected-(U2-LAT-Pad27)") (class "Default")
      (node (ref "U2") (pin "27") (pinfunction "LAT_27") (pintype "passive"))
    )
    (net (code "308") (name "unconnected-(U2-SCLK-Pad28)") (class "Default")
      (node (ref "U2") (pin "28") (pinfunction "SCLK_28") (pintype "passive"))
    )
    (net (code "309") (name "unconnected-(U2-SIN-Pad26)") (class "Default")
      (node (ref "U2") (pin "26") (pinfunction "SIN_26") (pintype "passive"))
    )
    (net (code "310") (name "unconnected-(U2-SOUT-Pad42)") (class "Default")
      (node (ref "U2") (pin "42") (pinfunction "SOUT_42") (pintype "passive"))
    )
    (net (code "311") (name "unconnected-(U3-BLANK-Pad29)") (class "Default")
      (node (ref "U3") (pin "29") (pinfunction "BLANK_29") (pintype "passive"))
    )
    (net (code "312") (name "unconnected-(U3-LAT-Pad27)") (class "Default")
      (node (ref "U3") (pin "27") (pinfunction "LAT_27") (pintype "passive"))
    )
    (net (code "313") (name "unconnected-(U3-OUTB7-Pad25)") (class "Default")
      (node (ref "U3") (pin "25") (pinfunction "OUTB7_25") (pintype "passive"))
    )
    (net (code "314") (name "unconnected-(U3-OUTG7-Pad24)") (class "Default")
      (node (ref "U3") (pin "24") (pinfunction "OUTG7_24") (pintype "passive"))
    )
    (net (code "315") (name "unconnected-(U3-OUTR7-Pad23)") (class "Default")
      (node (ref "U3") (pin "23") (pinfunction "OUTR7_23") (pintype "passive"))
    )
    (net (code "316") (name "unconnected-(U3-SCLK-Pad28)") (class "Default")
      (node (ref "U3") (pin "28") (pinfunction "SCLK_28") (pintype "passive"))
    )
    (net (code "317") (name "unconnected-(U3-SIN-Pad26)") (class "Default")
      (node (ref "U3") (pin "26") (pinfunction "SIN_26") (pintype "passive"))
    )
    (net (code "318") (name "unconnected-(U3-SOUT-Pad42)") (class "Default")
      (node (ref "U3") (pin "42") (pinfunction "SOUT_42") (pintype "passive"))
    )
    (net (code "319") (name "unconnected-(U4-BLANK-Pad29)") (class "Default")
      (node (ref "U4") (pin "29") (pinfunction "BLANK_29") (pintype "passive"))
    )
    (net (code "320") (name "unconnected-(U4-LAT-Pad27)") (class "Default")
      (node (ref "U4") (pin "27") (pinfunction "LAT_27") (pintype "passive"))
    )
    (net (code "321") (name "unconnected-(U4-OUTB9-Pad35)") (class "Default")
      (node (ref "U4") (pin "35") (pinfunction "OUTB9_35") (pintype "passive"))
    )
    (net (code "322") (name "unconnected-(U4-OUTB10-Pad38)") (class "Default")
      (node (ref "U4") (pin "38") (pinfunction "OUTB10_38") (pintype "passive"))
    )
    (net (code "323") (name "unconnected-(U4-OUTB11-Pad41)") (class "Default")
      (node (ref "U4") (pin "41") (pinfunction "OUTB11_41") (pintype "passive"))
    )
    (net (code "324") (name "unconnected-(U4-OUTG9-Pad34)") (class "Default")
      (node (ref "U4") (pin "34") (pinfunction "OUTG9_34") (pintype "passive"))
    )
    (net (code "325") (name "unconnected-(U4-OUTG10-Pad37)") (class "Default")
      (node (ref "U4") (pin "37") (pinfunction "OUTG10_37") (pintype "passive"))
    )
    (net (code "326") (name "unconnected-(U4-OUTG11-Pad40)") (class "Default")
      (node (ref "U4") (pin "40") (pinfunction "OUTG11_40") (pintype "passive"))
    )
    (net (code "327") (name "unconnected-(U4-OUTR9-Pad33)") (class "Default")
      (node (ref "U4") (pin "33") (pinfunction "OUTR9_33") (pintype "passive"))
    )
    (net (code "328") (name "unconnected-(U4-OUTR10-Pad36)") (class "Default")
      (node (ref "U4") (pin "36") (pinfunction "OUTR10_36") (pintype "passive"))
    )
    (net (code "329") (name "unconnected-(U4-OUTR11-Pad39)") (class "Default")
      (node (ref "U4") (pin "39") (pinfunction "OUTR11_39") (pintype "passive"))
    )
    (net (code "330") (name "unconnected-(U4-SCLK-Pad28)") (class "Default")
      (node (ref "U4") (pin "28") (pinfunction "SCLK_28") (pintype "passive"))
    )
    (net (code "331") (name "unconnected-(U4-SIN-Pad26)") (class "Default")
      (node (ref "U4") (pin "26") (pinfunction "SIN_26") (pintype "passive"))
    )
    (net (code "332") (name "unconnected-(U4-SOUT-Pad42)") (class "Default")
      (node (ref "U4") (pin "42") (pinfunction "SOUT_42") (pintype "passive"))
    )
    (net (code "333") (name "unconnected-(U5-BLANK-Pad29)") (class "Default")
      (node (ref "U5") (pin "29") (pinfunction "BLANK_29") (pintype "passive"))
    )
    (net (code "334") (name "unconnected-(U5-LAT-Pad27)") (class "Default")
      (node (ref "U5") (pin "27") (pinfunction "LAT_27") (pintype "passive"))
    )
    (net (code "335") (name "unconnected-(U5-OUTB11-Pad41)") (class "Default")
      (node (ref "U5") (pin "41") (pinfunction "OUTB11_41") (pintype "passive"))
    )
    (net (code "336") (name "unconnected-(U5-OUTB12-Pad46)") (class "Default")
      (node (ref "U5") (pin "46") (pinfunction "OUTB12_46") (pintype "passive"))
    )
    (net (code "337") (name "unconnected-(U5-OUTB13-Pad49)") (class "Default")
      (node (ref "U5") (pin "49") (pinfunction "OUTB13_49") (pintype "passive"))
    )
    (net (code "338") (name "unconnected-(U5-OUTB14-Pad52)") (class "Default")
      (node (ref "U5") (pin "52") (pinfunction "OUTB14_52") (pintype "passive"))
    )
    (net (code "339") (name "unconnected-(U5-OUTB15-Pad55)") (class "Default")
      (node (ref "U5") (pin "55") (pinfunction "OUTB15_55") (pintype "passive"))
    )
    (net (code "340") (name "unconnected-(U5-OUTG11-Pad40)") (class "Default")
      (node (ref "U5") (pin "40") (pinfunction "OUTG11_40") (pintype "passive"))
    )
    (net (code "341") (name "unconnected-(U5-OUTG12-Pad45)") (class "Default")
      (node (ref "U5") (pin "45") (pinfunction "OUTG12_45") (pintype "passive"))
    )
    (net (code "342") (name "unconnected-(U5-OUTG13-Pad48)") (class "Default")
      (node (ref "U5") (pin "48") (pinfunction "OUTG13_48") (pintype "passive"))
    )
    (net (code "343") (name "unconnected-(U5-OUTG14-Pad51)") (class "Default")
      (node (ref "U5") (pin "51") (pinfunction "OUTG14_51") (pintype "passive"))
    )
    (net (code "344") (name "unconnected-(U5-OUTG15-Pad54)") (class "Default")
      (node (ref "U5") (pin "54") (pinfunction "OUTG15_54") (pintype "passive"))
    )
    (net (code "345") (name "unconnected-(U5-OUTR11-Pad39)") (class "Default")
      (node (ref "U5") (pin "39") (pinfunction "OUTR11_39") (pintype "passive"))
    )
    (net (code "346") (name "unconnected-(U5-OUTR12-Pad44)") (class "Default")
      (node (ref "U5") (pin "44") (pinfunction "OUTR12_44") (pintype "passive"))
    )
    (net (code "347") (name "unconnected-(U5-OUTR13-Pad47)") (class "Default")
      (node (ref "U5") (pin "47") (pinfunction "OUTR13_47") (pintype "passive"))
    )
    (net (code "348") (name "unconnected-(U5-OUTR14-Pad50)") (class "Default")
      (node (ref "U5") (pin "50") (pinfunction "OUTR14_50") (pintype "passive"))
    )
    (net (code "349") (name "unconnected-(U5-OUTR15-Pad53)") (class "Default")
      (node (ref "U5") (pin "53") (pinfunction "OUTR15_53") (pintype "passive"))
    )
    (net (code "350") (name "unconnected-(U5-SCLK-Pad28)") (class "Default")
      (node (ref "U5") (pin "28") (pinfunction "SCLK_28") (pintype "passive"))
    )
    (net (code "351") (name "unconnected-(U5-SIN-Pad26)") (class "Default")
      (node (ref "U5") (pin "26") (pinfunction "SIN_26") (pintype "passive"))
    )
    (net (code "352") (name "unconnected-(U5-SOUT-Pad42)") (class "Default")
      (node (ref "U5") (pin "42") (pinfunction "SOUT_42") (pintype "passive"))
    )
    (net (code "353") (name "unconnected-(U6-BLANK-Pad29)") (class "Default")
      (node (ref "U6") (pin "29") (pinfunction "BLANK_29") (pintype "passive"))
    )
    (net (code "354") (name "unconnected-(U6-LAT-Pad27)") (class "Default")
      (node (ref "U6") (pin "27") (pinfunction "LAT_27") (pintype "passive"))
    )
    (net (code "355") (name "unconnected-(U6-OUTB12-Pad46)") (class "Default")
      (node (ref "U6") (pin "46") (pinfunction "OUTB12_46") (pintype "passive"))
    )
    (net (code "356") (name "unconnected-(U6-OUTB13-Pad49)") (class "Default")
      (node (ref "U6") (pin "49") (pinfunction "OUTB13_49") (pintype "passive"))
    )
    (net (code "357") (name "unconnected-(U6-OUTB14-Pad52)") (class "Default")
      (node (ref "U6") (pin "52") (pinfunction "OUTB14_52") (pintype "passive"))
    )
    (net (code "358") (name "unconnected-(U6-OUTG12-Pad45)") (class "Default")
      (node (ref "U6") (pin "45") (pinfunction "OUTG12_45") (pintype "passive"))
    )
    (net (code "359") (name "unconnected-(U6-OUTG13-Pad48)") (class "Default")
      (node (ref "U6") (pin "48") (pinfunction "OUTG13_48") (pintype "passive"))
    )
    (net (code "360") (name "unconnected-(U6-OUTG14-Pad51)") (class "Default")
      (node (ref "U6") (pin "51") (pinfunction "OUTG14_51") (pintype "passive"))
    )
    (net (code "361") (name "unconnected-(U6-OUTR12-Pad44)") (class "Default")
      (node (ref "U6") (pin "44") (pinfunction "OUTR12_44") (pintype "passive"))
    )
    (net (code "362") (name "unconnected-(U6-OUTR13-Pad47)") (class "Default")
      (node (ref "U6") (pin "47") (pinfunction "OUTR13_47") (pintype "passive"))
    )
    (net (code "363") (name "unconnected-(U6-OUTR14-Pad50)") (class "Default")
      (node (ref "U6") (pin "50") (pinfunction "OUTR14_50") (pintype "passive"))
    )
    (net (code "364") (name "unconnected-(U6-SCLK-Pad28)") (class "Default")
      (node (ref "U6") (pin "28") (pinfunction "SCLK_28") (pintype "passive"))
    )
    (net (code "365") (name "unconnected-(U6-SIN-Pad26)") (class "Default")
      (node (ref "U6") (pin "26") (pinfunction "SIN_26") (pintype "passive"))
    )
    (net (code "366") (name "unconnected-(U6-SOUT-Pad42)") (class "Default")
      (node (ref "U6") (pin "42") (pinfunction "SOUT_42") (pintype "passive"))
    )
    (net (code "367") (name "unconnected-(U7-BLANK-Pad29)") (class "Default")
      (node (ref "U7") (pin "29") (pinfunction "BLANK_29") (pintype "passive"))
    )
    (net (code "368") (name "unconnected-(U7-LAT-Pad27)") (class "Default")
      (node (ref "U7") (pin "27") (pinfunction "LAT_27") (pintype "passive"))
    )
    (net (code "369") (name "unconnected-(U7-OUTB15-Pad55)") (class "Default")
      (node (ref "U7") (pin "55") (pinfunction "OUTB15_55") (pintype "passive"))
    )
    (net (code "370") (name "unconnected-(U7-OUTG15-Pad54)") (class "Default")
      (node (ref "U7") (pin "54") (pinfunction "OUTG15_54") (pintype "passive"))
    )
    (net (code "371") (name "unconnected-(U7-OUTR15-Pad53)") (class "Default")
      (node (ref "U7") (pin "53") (pinfunction "OUTR15_53") (pintype "passive"))
    )
    (net (code "372") (name "unconnected-(U7-SCLK-Pad28)") (class "Default")
      (node (ref "U7") (pin "28") (pinfunction "SCLK_28") (pintype "passive"))
    )
    (net (code "373") (name "unconnected-(U7-SIN-Pad26)") (class "Default")
      (node (ref "U7") (pin "26") (pinfunction "SIN_26") (pintype "passive"))
    )
    (net (code "374") (name "unconnected-(U7-SOUT-Pad42)") (class "Default")
      (node (ref "U7") (pin "42") (pinfunction "SOUT_42") (pintype "passive"))
    )
  )
)
